# SWITCHING.net
KiCad netlist of a schematic drawn in Altium Designer
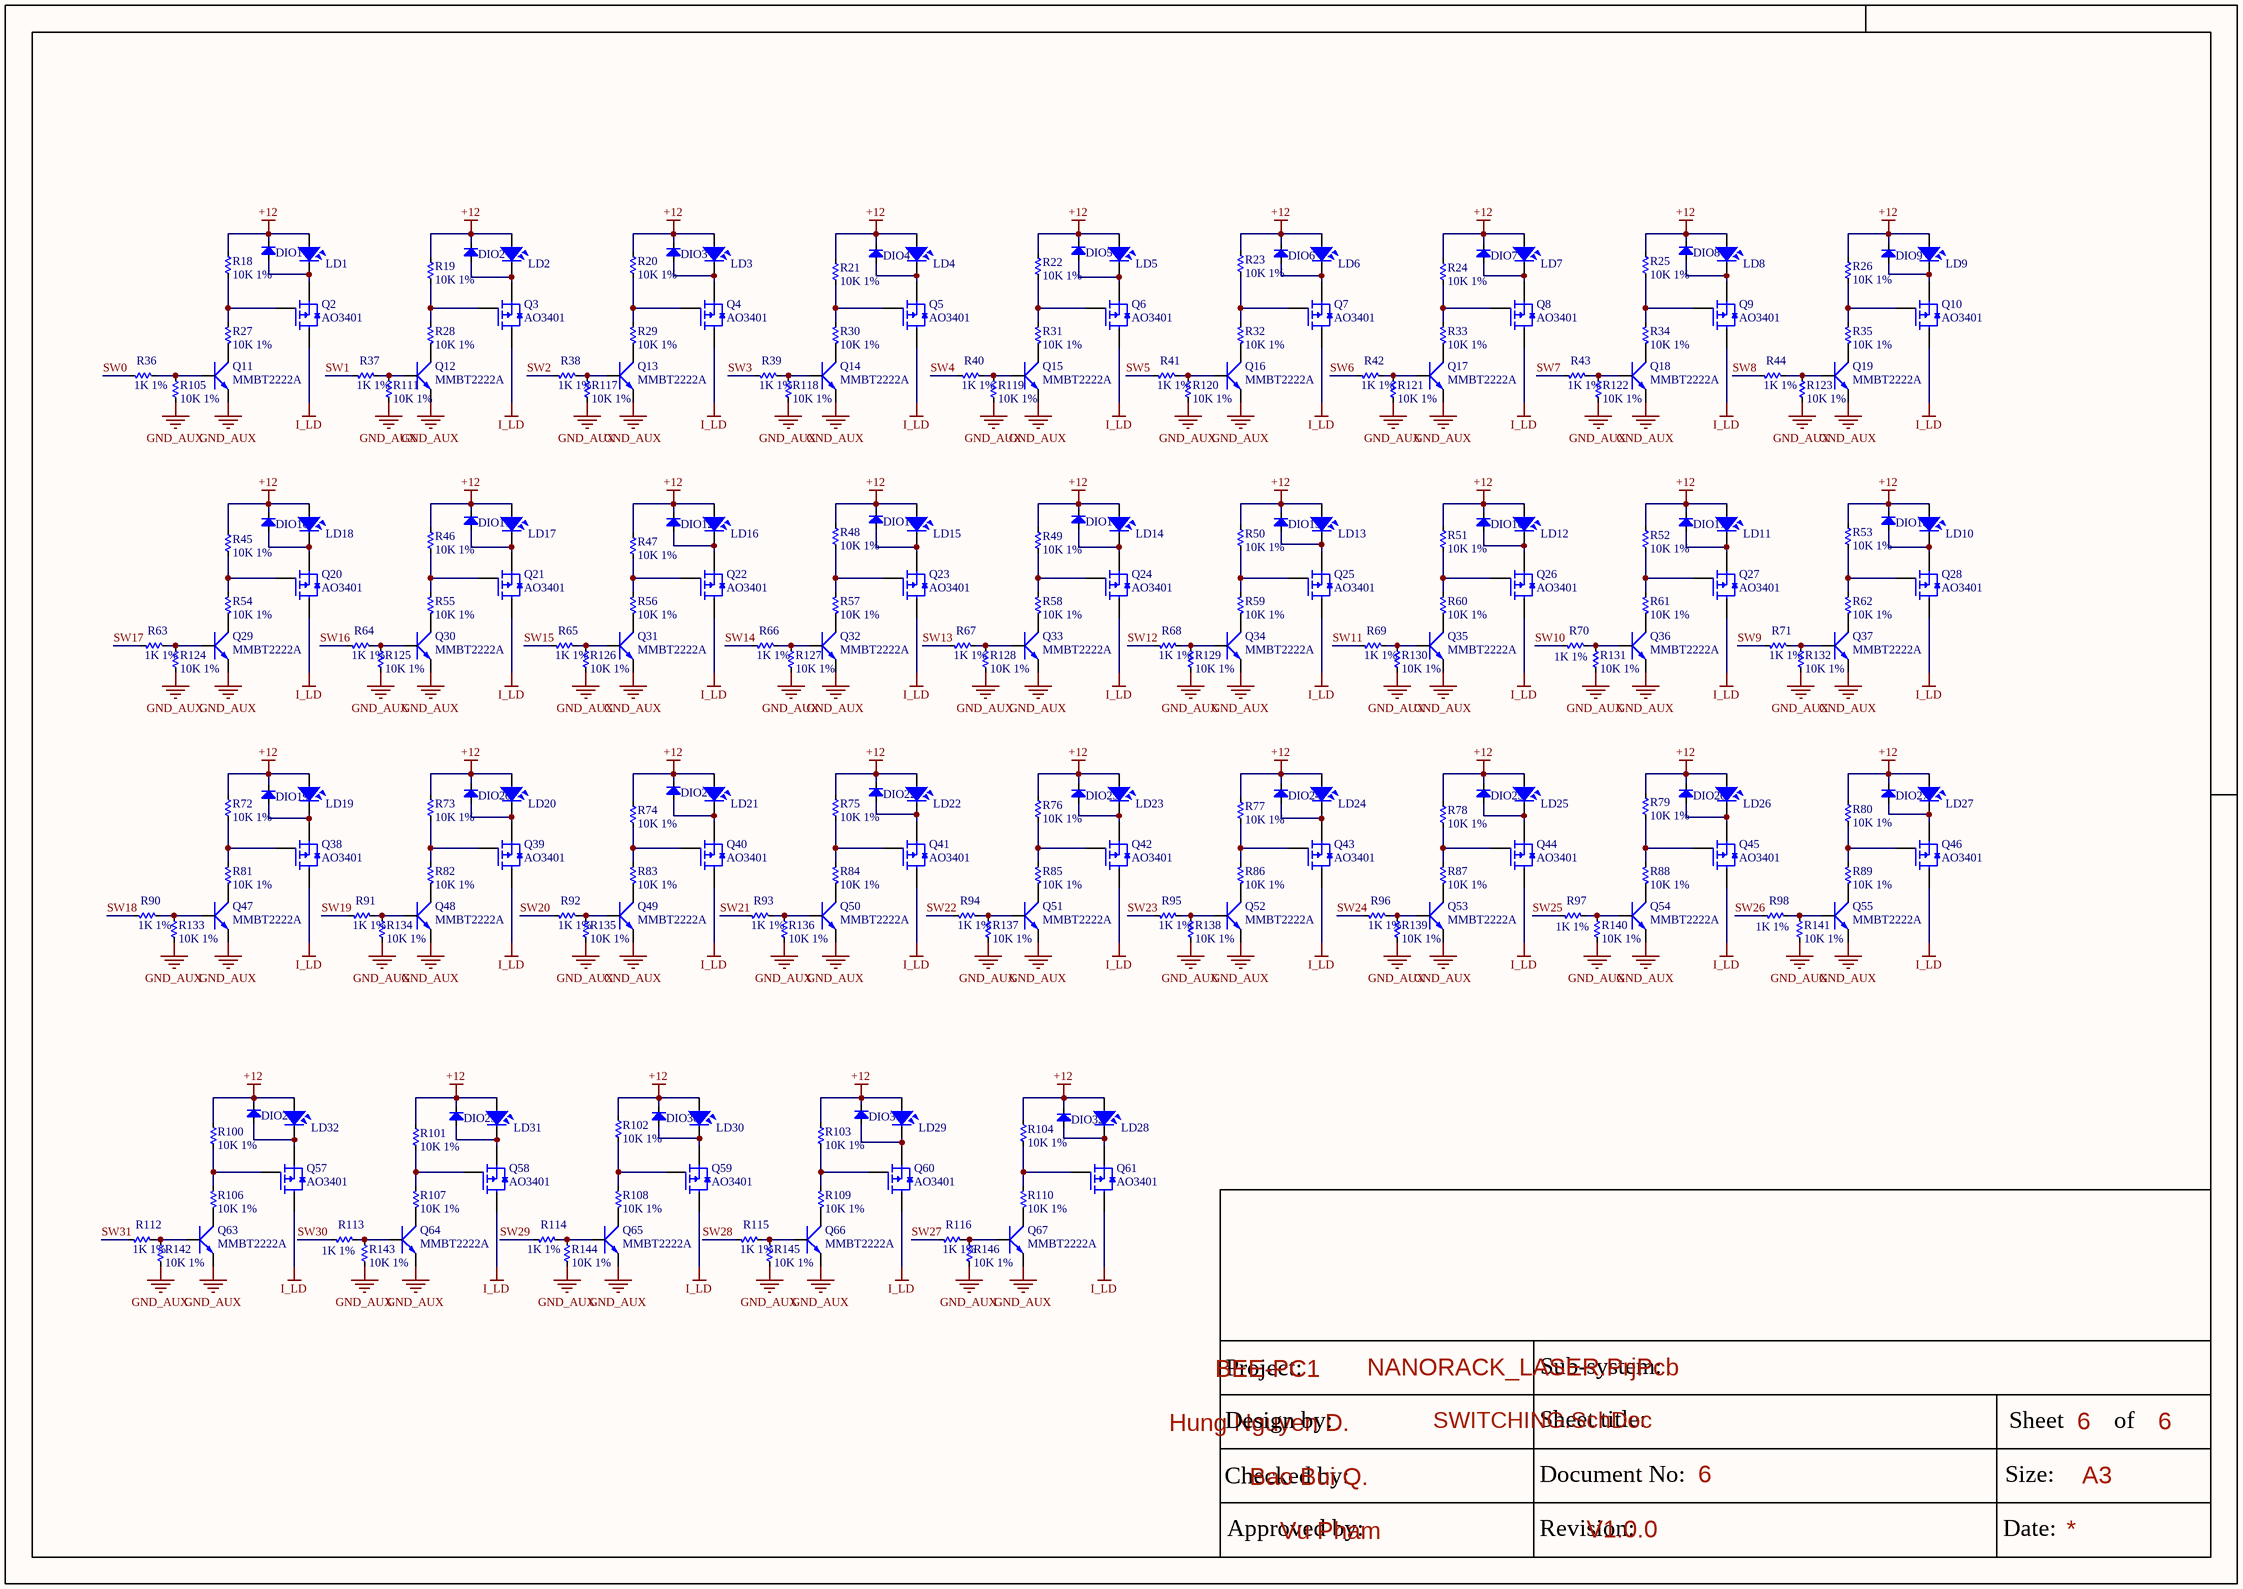
[diagram p0: SWITCHING.SchDoc]
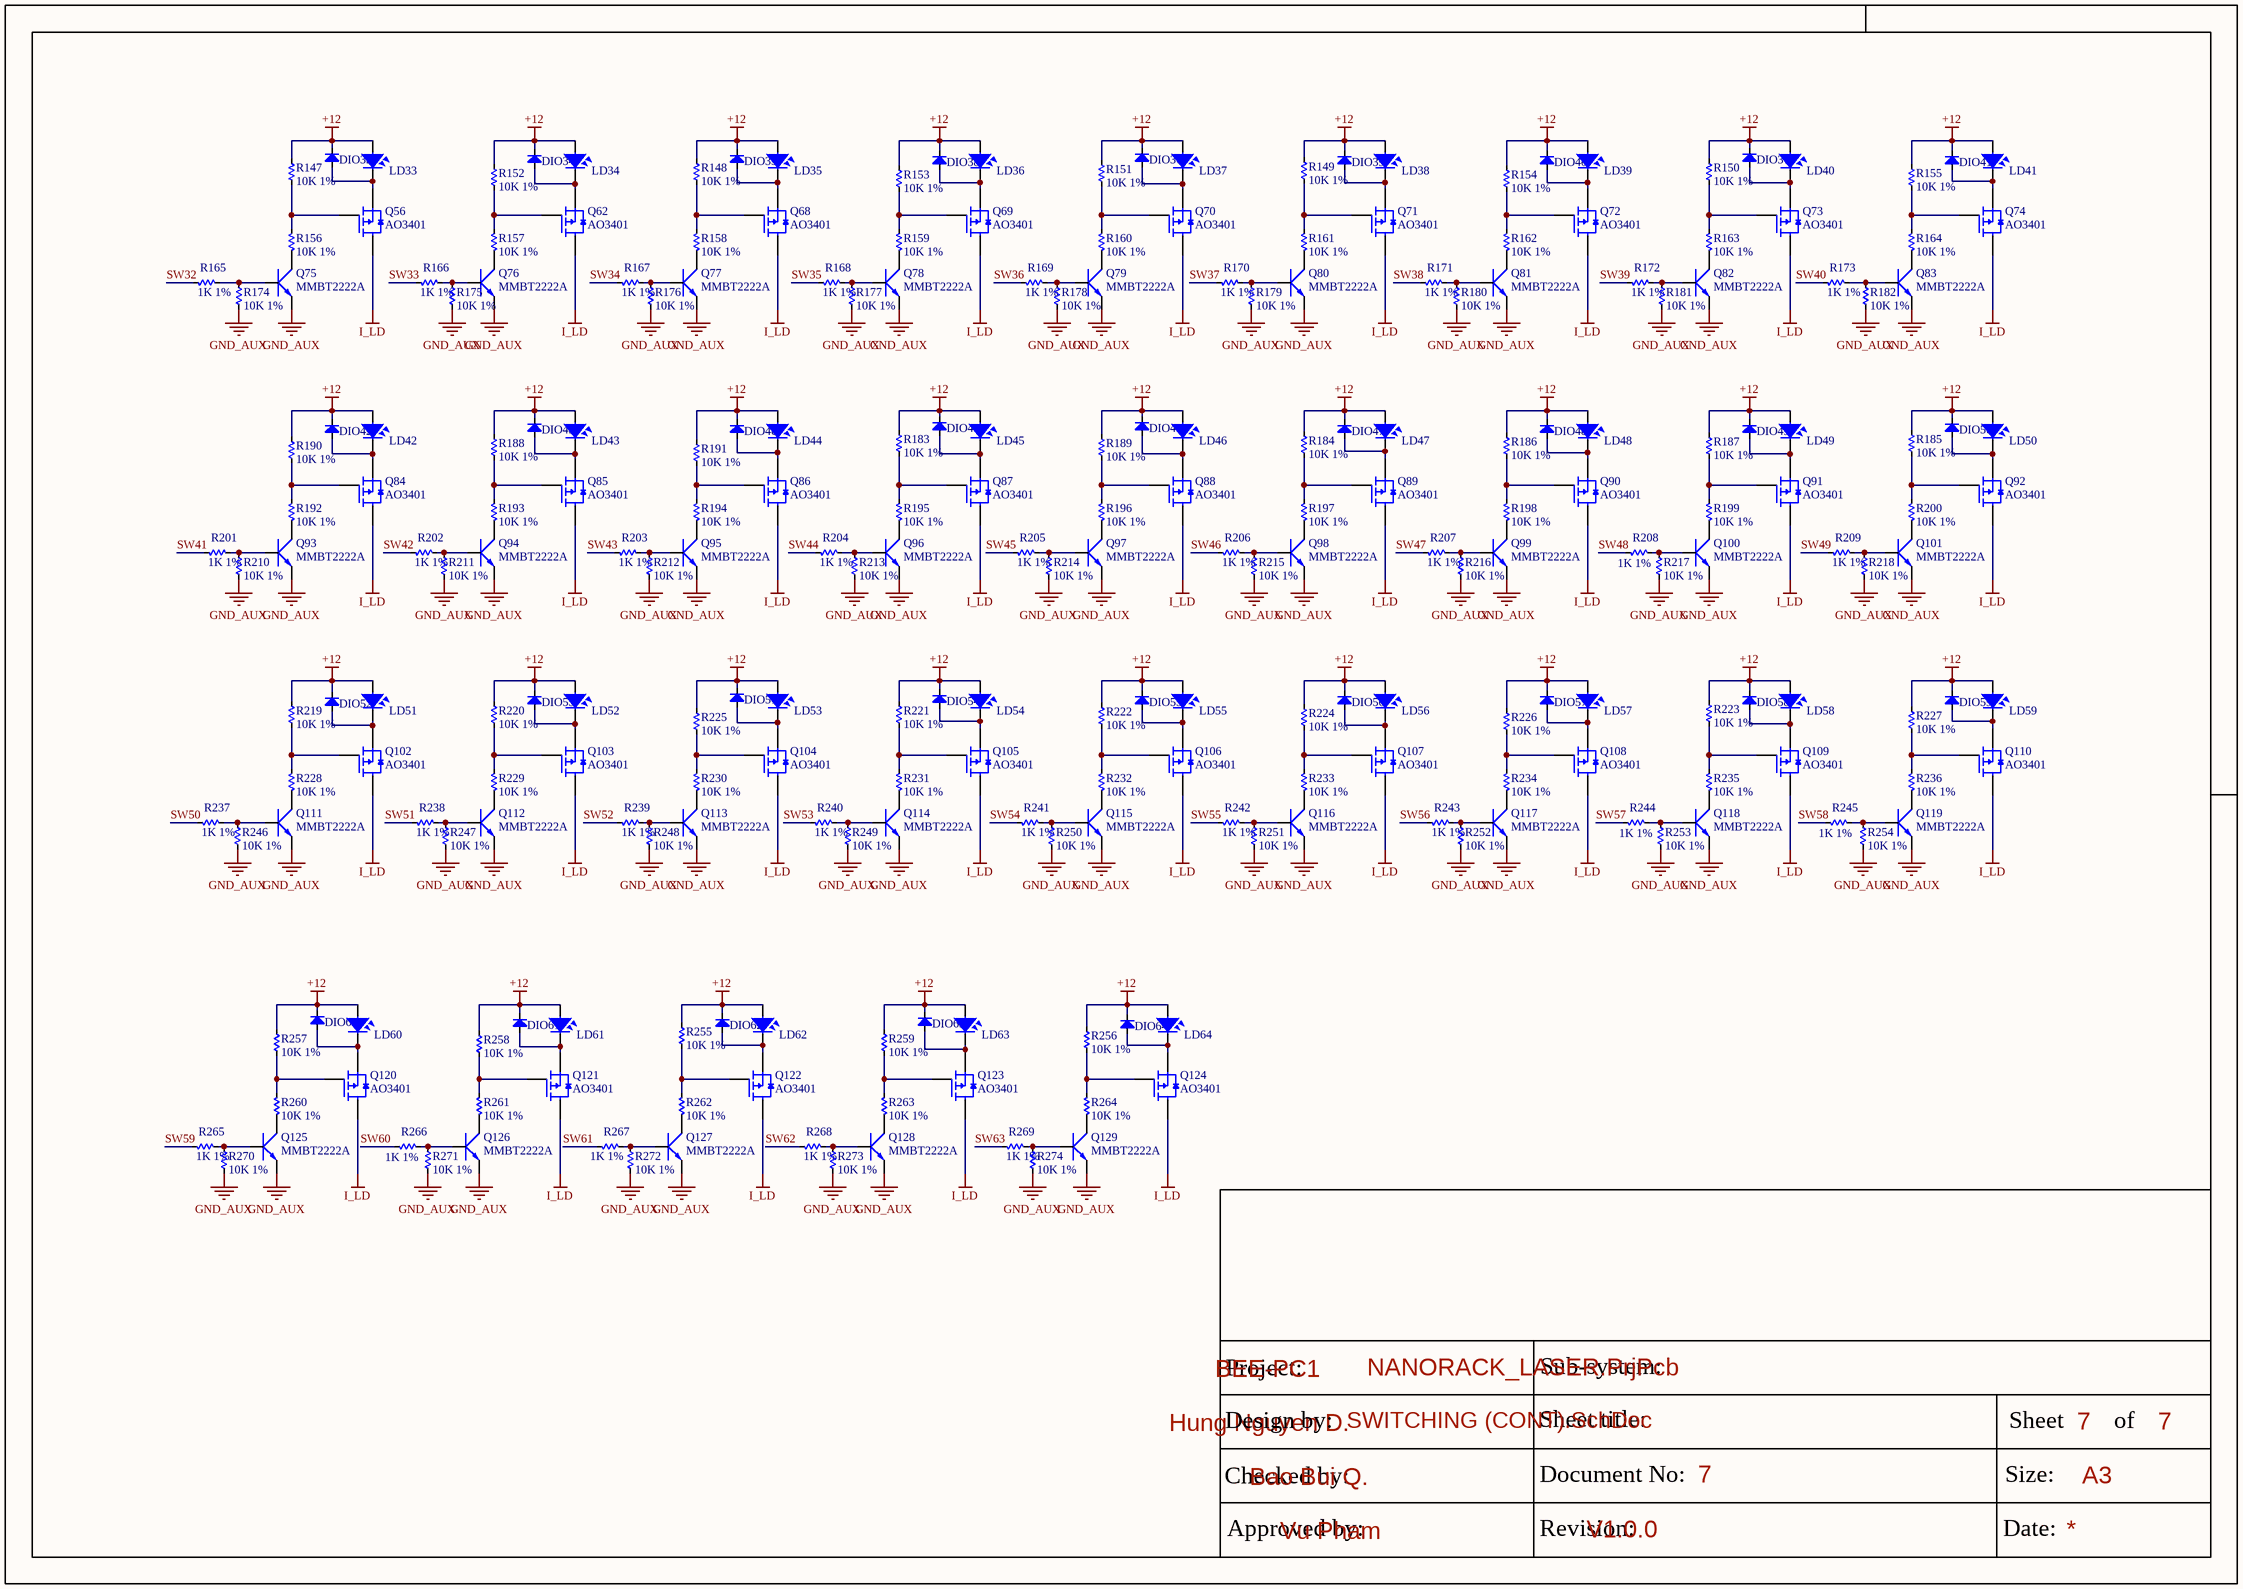
[diagram p1: SWITCHING (CONT).SchDoc]

(export (version "E")
  (design (tool "Eeschema 10.0.6"))
  (components
    (comp (ref "DIO33")
      (value "Diode SMD")
      (footprint "SOD23")
      (description "Default Diode")
      (fields (field (name "PUBLISHER") "Altium Limited"))
      (libsource (lib "Library") (part "Diode SMD"))
    )
    (comp (ref "DIO34")
      (value "Diode SMD")
      (footprint "SOD23")
      (description "Default Diode")
      (fields (field (name "PUBLISHER") "Altium Limited"))
      (libsource (lib "Library") (part "Diode SMD"))
    )
    (comp (ref "DIO35")
      (value "Diode SMD")
      (footprint "SOD23")
      (description "Default Diode")
      (fields (field (name "PUBLISHER") "Altium Limited"))
      (libsource (lib "Library") (part "Diode SMD"))
    )
    (comp (ref "DIO36")
      (value "Diode SMD")
      (footprint "SOD23")
      (description "Default Diode")
      (fields (field (name "PUBLISHER") "Altium Limited"))
      (libsource (lib "Library") (part "Diode SMD"))
    )
    (comp (ref "DIO37")
      (value "Diode SMD")
      (footprint "SOD23")
      (description "Default Diode")
      (fields (field (name "PUBLISHER") "Altium Limited"))
      (libsource (lib "Library") (part "Diode SMD"))
    )
    (comp (ref "DIO38")
      (value "Diode SMD")
      (footprint "SOD23")
      (description "Default Diode")
      (fields (field (name "PUBLISHER") "Altium Limited"))
      (libsource (lib "Library") (part "Diode SMD"))
    )
    (comp (ref "DIO39")
      (value "Diode SMD")
      (footprint "SOD23")
      (description "Default Diode")
      (fields (field (name "PUBLISHER") "Altium Limited"))
      (libsource (lib "Library") (part "Diode SMD"))
    )
    (comp (ref "DIO40")
      (value "Diode SMD")
      (footprint "SOD23")
      (description "Default Diode")
      (fields (field (name "PUBLISHER") "Altium Limited"))
      (libsource (lib "Library") (part "Diode SMD"))
    )
    (comp (ref "DIO41")
      (value "Diode SMD")
      (footprint "SOD23")
      (description "Default Diode")
      (fields (field (name "PUBLISHER") "Altium Limited"))
      (libsource (lib "Library") (part "Diode SMD"))
    )
    (comp (ref "DIO42")
      (value "Diode SMD")
      (footprint "SOD23")
      (description "Default Diode")
      (fields (field (name "PUBLISHER") "Altium Limited"))
      (libsource (lib "Library") (part "Diode SMD"))
    )
    (comp (ref "DIO43")
      (value "Diode SMD")
      (footprint "SOD23")
      (description "Default Diode")
      (fields (field (name "PUBLISHER") "Altium Limited"))
      (libsource (lib "Library") (part "Diode SMD"))
    )
    (comp (ref "DIO44")
      (value "Diode SMD")
      (footprint "SOD23")
      (description "Default Diode")
      (fields (field (name "PUBLISHER") "Altium Limited"))
      (libsource (lib "Library") (part "Diode SMD"))
    )
    (comp (ref "DIO45")
      (value "Diode SMD")
      (footprint "SOD23")
      (description "Default Diode")
      (fields (field (name "PUBLISHER") "Altium Limited"))
      (libsource (lib "Library") (part "Diode SMD"))
    )
    (comp (ref "DIO46")
      (value "Diode SMD")
      (footprint "SOD23")
      (description "Default Diode")
      (fields (field (name "PUBLISHER") "Altium Limited"))
      (libsource (lib "Library") (part "Diode SMD"))
    )
    (comp (ref "DIO47")
      (value "Diode SMD")
      (footprint "SOD23")
      (description "Default Diode")
      (fields (field (name "PUBLISHER") "Altium Limited"))
      (libsource (lib "Library") (part "Diode SMD"))
    )
    (comp (ref "DIO48")
      (value "Diode SMD")
      (footprint "SOD23")
      (description "Default Diode")
      (fields (field (name "PUBLISHER") "Altium Limited"))
      (libsource (lib "Library") (part "Diode SMD"))
    )
    (comp (ref "DIO49")
      (value "Diode SMD")
      (footprint "SOD23")
      (description "Default Diode")
      (fields (field (name "PUBLISHER") "Altium Limited"))
      (libsource (lib "Library") (part "Diode SMD"))
    )
    (comp (ref "DIO50")
      (value "Diode SMD")
      (footprint "SOD23")
      (description "Default Diode")
      (fields (field (name "PUBLISHER") "Altium Limited"))
      (libsource (lib "Library") (part "Diode SMD"))
    )
    (comp (ref "DIO51")
      (value "Diode SMD")
      (footprint "SOD23")
      (description "Default Diode")
      (fields (field (name "PUBLISHER") "Altium Limited"))
      (libsource (lib "Library") (part "Diode SMD"))
    )
    (comp (ref "DIO52")
      (value "Diode SMD")
      (footprint "SOD23")
      (description "Default Diode")
      (fields (field (name "PUBLISHER") "Altium Limited"))
      (libsource (lib "Library") (part "Diode SMD"))
    )
    (comp (ref "DIO53")
      (value "Diode SMD")
      (footprint "SOD23")
      (description "Default Diode")
      (fields (field (name "PUBLISHER") "Altium Limited"))
      (libsource (lib "Library") (part "Diode SMD"))
    )
    (comp (ref "DIO54")
      (value "Diode SMD")
      (footprint "SOD23")
      (description "Default Diode")
      (fields (field (name "PUBLISHER") "Altium Limited"))
      (libsource (lib "Library") (part "Diode SMD"))
    )
    (comp (ref "DIO55")
      (value "Diode SMD")
      (footprint "SOD23")
      (description "Default Diode")
      (fields (field (name "PUBLISHER") "Altium Limited"))
      (libsource (lib "Library") (part "Diode SMD"))
    )
    (comp (ref "DIO56")
      (value "Diode SMD")
      (footprint "SOD23")
      (description "Default Diode")
      (fields (field (name "PUBLISHER") "Altium Limited"))
      (libsource (lib "Library") (part "Diode SMD"))
    )
    (comp (ref "DIO57")
      (value "Diode SMD")
      (footprint "SOD23")
      (description "Default Diode")
      (fields (field (name "PUBLISHER") "Altium Limited"))
      (libsource (lib "Library") (part "Diode SMD"))
    )
    (comp (ref "DIO58")
      (value "Diode SMD")
      (footprint "SOD23")
      (description "Default Diode")
      (fields (field (name "PUBLISHER") "Altium Limited"))
      (libsource (lib "Library") (part "Diode SMD"))
    )
    (comp (ref "DIO59")
      (value "Diode SMD")
      (footprint "SOD23")
      (description "Default Diode")
      (fields (field (name "PUBLISHER") "Altium Limited"))
      (libsource (lib "Library") (part "Diode SMD"))
    )
    (comp (ref "DIO60")
      (value "Diode SMD")
      (footprint "SOD23")
      (description "Default Diode")
      (fields (field (name "PUBLISHER") "Altium Limited"))
      (libsource (lib "Library") (part "Diode SMD"))
    )
    (comp (ref "DIO61")
      (value "Diode SMD")
      (footprint "SOD23")
      (description "Default Diode")
      (fields (field (name "PUBLISHER") "Altium Limited"))
      (libsource (lib "Library") (part "Diode SMD"))
    )
    (comp (ref "DIO62")
      (value "Diode SMD")
      (footprint "SOD23")
      (description "Default Diode")
      (fields (field (name "PUBLISHER") "Altium Limited"))
      (libsource (lib "Library") (part "Diode SMD"))
    )
    (comp (ref "DIO63")
      (value "Diode SMD")
      (footprint "SOD23")
      (description "Default Diode")
      (fields (field (name "PUBLISHER") "Altium Limited"))
      (libsource (lib "Library") (part "Diode SMD"))
    )
    (comp (ref "DIO64")
      (value "Diode SMD")
      (footprint "SOD23")
      (description "Default Diode")
      (fields (field (name "PUBLISHER") "Altium Limited"))
      (libsource (lib "Library") (part "Diode SMD"))
    )
    (comp (ref "LD33") (value "LaserDiode") (footprint "LASER") (libsource (lib "Library") (part "LD")))
    (comp (ref "LD34") (value "LaserDiode") (footprint "LASER") (libsource (lib "Library") (part "LD")))
    (comp (ref "LD35") (value "LaserDiode") (footprint "LASER") (libsource (lib "Library") (part "LD")))
    (comp (ref "LD36") (value "LaserDiode") (footprint "LASER") (libsource (lib "Library") (part "LD")))
    (comp (ref "LD37") (value "LaserDiode") (footprint "LASER") (libsource (lib "Library") (part "LD")))
    (comp (ref "LD38") (value "LaserDiode") (footprint "LASER") (libsource (lib "Library") (part "LD")))
    (comp (ref "LD39") (value "LaserDiode") (footprint "LASER") (libsource (lib "Library") (part "LD")))
    (comp (ref "LD40") (value "LaserDiode") (footprint "LASER") (libsource (lib "Library") (part "LD")))
    (comp (ref "LD41") (value "LaserDiode") (footprint "LASER") (libsource (lib "Library") (part "LD")))
    (comp (ref "LD42") (value "LaserDiode") (footprint "LASER") (libsource (lib "Library") (part "LD")))
    (comp (ref "LD43") (value "LaserDiode") (footprint "LASER") (libsource (lib "Library") (part "LD")))
    (comp (ref "LD44") (value "LaserDiode") (footprint "LASER") (libsource (lib "Library") (part "LD")))
    (comp (ref "LD45") (value "LaserDiode") (footprint "LASER") (libsource (lib "Library") (part "LD")))
    (comp (ref "LD46") (value "LaserDiode") (footprint "LASER") (libsource (lib "Library") (part "LD")))
    (comp (ref "LD47") (value "LaserDiode") (footprint "LASER") (libsource (lib "Library") (part "LD")))
    (comp (ref "LD48") (value "LaserDiode") (footprint "LASER") (libsource (lib "Library") (part "LD")))
    (comp (ref "LD49") (value "LaserDiode") (footprint "LASER") (libsource (lib "Library") (part "LD")))
    (comp (ref "LD50") (value "LaserDiode") (footprint "LASER") (libsource (lib "Library") (part "LD")))
    (comp (ref "LD51") (value "LaserDiode") (footprint "LASER") (libsource (lib "Library") (part "LD")))
    (comp (ref "LD52") (value "LaserDiode") (footprint "LASER") (libsource (lib "Library") (part "LD")))
    (comp (ref "LD53") (value "LaserDiode") (footprint "LASER") (libsource (lib "Library") (part "LD")))
    (comp (ref "LD54") (value "LaserDiode") (footprint "LASER") (libsource (lib "Library") (part "LD")))
    (comp (ref "LD55") (value "LaserDiode") (footprint "LASER") (libsource (lib "Library") (part "LD")))
    (comp (ref "LD56") (value "LaserDiode") (footprint "LASER") (libsource (lib "Library") (part "LD")))
    (comp (ref "LD57") (value "LaserDiode") (footprint "LASER") (libsource (lib "Library") (part "LD")))
    (comp (ref "LD58") (value "LaserDiode") (footprint "LASER") (libsource (lib "Library") (part "LD")))
    (comp (ref "LD59") (value "LaserDiode") (footprint "LASER") (libsource (lib "Library") (part "LD")))
    (comp (ref "LD60") (value "LaserDiode") (footprint "LASER") (libsource (lib "Library") (part "LD")))
    (comp (ref "LD61") (value "LaserDiode") (footprint "LASER") (libsource (lib "Library") (part "LD")))
    (comp (ref "LD62") (value "LaserDiode") (footprint "LASER") (libsource (lib "Library") (part "LD")))
    (comp (ref "LD63") (value "LaserDiode") (footprint "LASER") (libsource (lib "Library") (part "LD")))
    (comp (ref "LD64") (value "LaserDiode") (footprint "LASER") (libsource (lib "Library") (part "LD")))
    (comp (ref "Q56") (value "AO3401") (footprint "SOT23-123") (libsource (lib "Library") (part "FET-P")))
    (comp (ref "Q62") (value "AO3401") (footprint "SOT23-123") (libsource (lib "Library") (part "FET-P")))
    (comp (ref "Q68") (value "AO3401") (footprint "SOT23-123") (libsource (lib "Library") (part "FET-P")))
    (comp (ref "Q69") (value "AO3401") (footprint "SOT23-123") (libsource (lib "Library") (part "FET-P")))
    (comp (ref "Q70") (value "AO3401") (footprint "SOT23-123") (libsource (lib "Library") (part "FET-P")))
    (comp (ref "Q71") (value "AO3401") (footprint "SOT23-123") (libsource (lib "Library") (part "FET-P")))
    (comp (ref "Q72") (value "AO3401") (footprint "SOT23-123") (libsource (lib "Library") (part "FET-P")))
    (comp (ref "Q73") (value "AO3401") (footprint "SOT23-123") (libsource (lib "Library") (part "FET-P")))
    (comp (ref "Q74") (value "AO3401") (footprint "SOT23-123") (libsource (lib "Library") (part "FET-P")))
    (comp (ref "Q75")
      (value "MMBT2222A")
      (footprint "SOT23-132")
      (description "SOT23-3")
      (libsource (lib "Library") (part "2SC1815"))
    )
    (comp (ref "Q76")
      (value "MMBT2222A")
      (footprint "SOT23-132")
      (description "SOT23-3")
      (libsource (lib "Library") (part "2SC1815"))
    )
    (comp (ref "Q77")
      (value "MMBT2222A")
      (footprint "SOT23-132")
      (description "SOT23-3")
      (libsource (lib "Library") (part "2SC1815"))
    )
    (comp (ref "Q78")
      (value "MMBT2222A")
      (footprint "SOT23-132")
      (description "SOT23-3")
      (libsource (lib "Library") (part "2SC1815"))
    )
    (comp (ref "Q79")
      (value "MMBT2222A")
      (footprint "SOT23-132")
      (description "SOT23-3")
      (libsource (lib "Library") (part "2SC1815"))
    )
    (comp (ref "Q80")
      (value "MMBT2222A")
      (footprint "SOT23-132")
      (description "SOT23-3")
      (libsource (lib "Library") (part "2SC1815"))
    )
    (comp (ref "Q81")
      (value "MMBT2222A")
      (footprint "SOT23-132")
      (description "SOT23-3")
      (libsource (lib "Library") (part "2SC1815"))
    )
    (comp (ref "Q82")
      (value "MMBT2222A")
      (footprint "SOT23-132")
      (description "SOT23-3")
      (libsource (lib "Library") (part "2SC1815"))
    )
    (comp (ref "Q83")
      (value "MMBT2222A")
      (footprint "SOT23-132")
      (description "SOT23-3")
      (libsource (lib "Library") (part "2SC1815"))
    )
    (comp (ref "Q84") (value "AO3401") (footprint "SOT23-123") (libsource (lib "Library") (part "FET-P")))
    (comp (ref "Q85") (value "AO3401") (footprint "SOT23-123") (libsource (lib "Library") (part "FET-P")))
    (comp (ref "Q86") (value "AO3401") (footprint "SOT23-123") (libsource (lib "Library") (part "FET-P")))
    (comp (ref "Q87") (value "AO3401") (footprint "SOT23-123") (libsource (lib "Library") (part "FET-P")))
    (comp (ref "Q88") (value "AO3401") (footprint "SOT23-123") (libsource (lib "Library") (part "FET-P")))
    (comp (ref "Q89") (value "AO3401") (footprint "SOT23-123") (libsource (lib "Library") (part "FET-P")))
    (comp (ref "Q90") (value "AO3401") (footprint "SOT23-123") (libsource (lib "Library") (part "FET-P")))
    (comp (ref "Q91") (value "AO3401") (footprint "SOT23-123") (libsource (lib "Library") (part "FET-P")))
    (comp (ref "Q92") (value "AO3401") (footprint "SOT23-123") (libsource (lib "Library") (part "FET-P")))
    (comp (ref "Q93")
      (value "MMBT2222A")
      (footprint "SOT23-132")
      (description "SOT23-3")
      (libsource (lib "Library") (part "2SC1815"))
    )
    (comp (ref "Q94")
      (value "MMBT2222A")
      (footprint "SOT23-132")
      (description "SOT23-3")
      (libsource (lib "Library") (part "2SC1815"))
    )
    (comp (ref "Q95")
      (value "MMBT2222A")
      (footprint "SOT23-132")
      (description "SOT23-3")
      (libsource (lib "Library") (part "2SC1815"))
    )
    (comp (ref "Q96")
      (value "MMBT2222A")
      (footprint "SOT23-132")
      (description "SOT23-3")
      (libsource (lib "Library") (part "2SC1815"))
    )
    (comp (ref "Q97")
      (value "MMBT2222A")
      (footprint "SOT23-132")
      (description "SOT23-3")
      (libsource (lib "Library") (part "2SC1815"))
    )
    (comp (ref "Q98")
      (value "MMBT2222A")
      (footprint "SOT23-132")
      (description "SOT23-3")
      (libsource (lib "Library") (part "2SC1815"))
    )
    (comp (ref "Q99")
      (value "MMBT2222A")
      (footprint "SOT23-132")
      (description "SOT23-3")
      (libsource (lib "Library") (part "2SC1815"))
    )
    (comp (ref "Q100")
      (value "MMBT2222A")
      (footprint "SOT23-132")
      (description "SOT23-3")
      (libsource (lib "Library") (part "2SC1815"))
    )
    (comp (ref "Q101")
      (value "MMBT2222A")
      (footprint "SOT23-132")
      (description "SOT23-3")
      (libsource (lib "Library") (part "2SC1815"))
    )
    (comp (ref "Q102") (value "AO3401") (footprint "SOT23-123") (libsource (lib "Library") (part "FET-P")))
    (comp (ref "Q103") (value "AO3401") (footprint "SOT23-123") (libsource (lib "Library") (part "FET-P")))
    (comp (ref "Q104") (value "AO3401") (footprint "SOT23-123") (libsource (lib "Library") (part "FET-P")))
    (comp (ref "Q105") (value "AO3401") (footprint "SOT23-123") (libsource (lib "Library") (part "FET-P")))
    (comp (ref "Q106") (value "AO3401") (footprint "SOT23-123") (libsource (lib "Library") (part "FET-P")))
    (comp (ref "Q107") (value "AO3401") (footprint "SOT23-123") (libsource (lib "Library") (part "FET-P")))
    (comp (ref "Q108") (value "AO3401") (footprint "SOT23-123") (libsource (lib "Library") (part "FET-P")))
    (comp (ref "Q109") (value "AO3401") (footprint "SOT23-123") (libsource (lib "Library") (part "FET-P")))
    (comp (ref "Q110") (value "AO3401") (footprint "SOT23-123") (libsource (lib "Library") (part "FET-P")))
    (comp (ref "Q111")
      (value "MMBT2222A")
      (footprint "SOT23-132")
      (description "SOT23-3")
      (libsource (lib "Library") (part "2SC1815"))
    )
    (comp (ref "Q112")
      (value "MMBT2222A")
      (footprint "SOT23-132")
      (description "SOT23-3")
      (libsource (lib "Library") (part "2SC1815"))
    )
    (comp (ref "Q113")
      (value "MMBT2222A")
      (footprint "SOT23-132")
      (description "SOT23-3")
      (libsource (lib "Library") (part "2SC1815"))
    )
    (comp (ref "Q114")
      (value "MMBT2222A")
      (footprint "SOT23-132")
      (description "SOT23-3")
      (libsource (lib "Library") (part "2SC1815"))
    )
    (comp (ref "Q115")
      (value "MMBT2222A")
      (footprint "SOT23-132")
      (description "SOT23-3")
      (libsource (lib "Library") (part "2SC1815"))
    )
    (comp (ref "Q116")
      (value "MMBT2222A")
      (footprint "SOT23-132")
      (description "SOT23-3")
      (libsource (lib "Library") (part "2SC1815"))
    )
    (comp (ref "Q117")
      (value "MMBT2222A")
      (footprint "SOT23-132")
      (description "SOT23-3")
      (libsource (lib "Library") (part "2SC1815"))
    )
    (comp (ref "Q118")
      (value "MMBT2222A")
      (footprint "SOT23-132")
      (description "SOT23-3")
      (libsource (lib "Library") (part "2SC1815"))
    )
    (comp (ref "Q119")
      (value "MMBT2222A")
      (footprint "SOT23-132")
      (description "SOT23-3")
      (libsource (lib "Library") (part "2SC1815"))
    )
    (comp (ref "Q120") (value "AO3401") (footprint "SOT23-123") (libsource (lib "Library") (part "FET-P")))
    (comp (ref "Q121") (value "AO3401") (footprint "SOT23-123") (libsource (lib "Library") (part "FET-P")))
    (comp (ref "Q122") (value "AO3401") (footprint "SOT23-123") (libsource (lib "Library") (part "FET-P")))
    (comp (ref "Q123") (value "AO3401") (footprint "SOT23-123") (libsource (lib "Library") (part "FET-P")))
    (comp (ref "Q124") (value "AO3401") (footprint "SOT23-123") (libsource (lib "Library") (part "FET-P")))
    (comp (ref "Q125")
      (value "MMBT2222A")
      (footprint "SOT23-132")
      (description "SOT23-3")
      (libsource (lib "Library") (part "2SC1815"))
    )
    (comp (ref "Q126")
      (value "MMBT2222A")
      (footprint "SOT23-132")
      (description "SOT23-3")
      (libsource (lib "Library") (part "2SC1815"))
    )
    (comp (ref "Q127")
      (value "MMBT2222A")
      (footprint "SOT23-132")
      (description "SOT23-3")
      (libsource (lib "Library") (part "2SC1815"))
    )
    (comp (ref "Q128")
      (value "MMBT2222A")
      (footprint "SOT23-132")
      (description "SOT23-3")
      (libsource (lib "Library") (part "2SC1815"))
    )
    (comp (ref "Q129")
      (value "MMBT2222A")
      (footprint "SOT23-132")
      (description "SOT23-3")
      (libsource (lib "Library") (part "2SC1815"))
    )
    (comp (ref "R147")
      (value "10K 1%")
      (footprint "RES-SMD-0603")
      (description "0603")
      (fields
        (field (name "MANUFACTURER") "Generic Components")
        (field (name "PUBLISHER") "Altium Hobart Technology Centre")
      )
      (libsource (lib "Library") (part "Res-SMD"))
    )
    (comp (ref "R148")
      (value "10K 1%")
      (footprint "RES-SMD-0603")
      (description "0603")
      (fields
        (field (name "MANUFACTURER") "Generic Components")
        (field (name "PUBLISHER") "Altium Hobart Technology Centre")
      )
      (libsource (lib "Library") (part "Res-SMD"))
    )
    (comp (ref "R149")
      (value "10K 1%")
      (footprint "RES-SMD-0603")
      (description "0603")
      (fields
        (field (name "MANUFACTURER") "Generic Components")
        (field (name "PUBLISHER") "Altium Hobart Technology Centre")
      )
      (libsource (lib "Library") (part "Res-SMD"))
    )
    (comp (ref "R150")
      (value "10K 1%")
      (footprint "RES-SMD-0603")
      (description "0603")
      (fields
        (field (name "MANUFACTURER") "Generic Components")
        (field (name "PUBLISHER") "Altium Hobart Technology Centre")
      )
      (libsource (lib "Library") (part "Res-SMD"))
    )
    (comp (ref "R151")
      (value "10K 1%")
      (footprint "RES-SMD-0603")
      (description "0603")
      (fields
        (field (name "MANUFACTURER") "Generic Components")
        (field (name "PUBLISHER") "Altium Hobart Technology Centre")
      )
      (libsource (lib "Library") (part "Res-SMD"))
    )
    (comp (ref "R152")
      (value "10K 1%")
      (footprint "RES-SMD-0603")
      (description "0603")
      (fields
        (field (name "MANUFACTURER") "Generic Components")
        (field (name "PUBLISHER") "Altium Hobart Technology Centre")
      )
      (libsource (lib "Library") (part "Res-SMD"))
    )
    (comp (ref "R153")
      (value "10K 1%")
      (footprint "RES-SMD-0603")
      (description "0603")
      (fields
        (field (name "MANUFACTURER") "Generic Components")
        (field (name "PUBLISHER") "Altium Hobart Technology Centre")
      )
      (libsource (lib "Library") (part "Res-SMD"))
    )
    (comp (ref "R154")
      (value "10K 1%")
      (footprint "RES-SMD-0603")
      (description "0603")
      (fields
        (field (name "MANUFACTURER") "Generic Components")
        (field (name "PUBLISHER") "Altium Hobart Technology Centre")
      )
      (libsource (lib "Library") (part "Res-SMD"))
    )
    (comp (ref "R155")
      (value "10K 1%")
      (footprint "RES-SMD-0603")
      (description "0603")
      (fields
        (field (name "MANUFACTURER") "Generic Components")
        (field (name "PUBLISHER") "Altium Hobart Technology Centre")
      )
      (libsource (lib "Library") (part "Res-SMD"))
    )
    (comp (ref "R156")
      (value "10K 1%")
      (footprint "RES-SMD-0603")
      (description "0603")
      (fields
        (field (name "MANUFACTURER") "Generic Components")
        (field (name "PUBLISHER") "Altium Hobart Technology Centre")
      )
      (libsource (lib "Library") (part "Res-SMD"))
    )
    (comp (ref "R157")
      (value "10K 1%")
      (footprint "RES-SMD-0603")
      (description "0603")
      (fields
        (field (name "MANUFACTURER") "Generic Components")
        (field (name "PUBLISHER") "Altium Hobart Technology Centre")
      )
      (libsource (lib "Library") (part "Res-SMD"))
    )
    (comp (ref "R158")
      (value "10K 1%")
      (footprint "RES-SMD-0603")
      (description "0603")
      (fields
        (field (name "MANUFACTURER") "Generic Components")
        (field (name "PUBLISHER") "Altium Hobart Technology Centre")
      )
      (libsource (lib "Library") (part "Res-SMD"))
    )
    (comp (ref "R159")
      (value "10K 1%")
      (footprint "RES-SMD-0603")
      (description "0603")
      (fields
        (field (name "MANUFACTURER") "Generic Components")
        (field (name "PUBLISHER") "Altium Hobart Technology Centre")
      )
      (libsource (lib "Library") (part "Res-SMD"))
    )
    (comp (ref "R160")
      (value "10K 1%")
      (footprint "RES-SMD-0603")
      (description "0603")
      (fields
        (field (name "MANUFACTURER") "Generic Components")
        (field (name "PUBLISHER") "Altium Hobart Technology Centre")
      )
      (libsource (lib "Library") (part "Res-SMD"))
    )
    (comp (ref "R161")
      (value "10K 1%")
      (footprint "RES-SMD-0603")
      (description "0603")
      (fields
        (field (name "MANUFACTURER") "Generic Components")
        (field (name "PUBLISHER") "Altium Hobart Technology Centre")
      )
      (libsource (lib "Library") (part "Res-SMD"))
    )
    (comp (ref "R162")
      (value "10K 1%")
      (footprint "RES-SMD-0603")
      (description "0603")
      (fields
        (field (name "MANUFACTURER") "Generic Components")
        (field (name "PUBLISHER") "Altium Hobart Technology Centre")
      )
      (libsource (lib "Library") (part "Res-SMD"))
    )
    (comp (ref "R163")
      (value "10K 1%")
      (footprint "RES-SMD-0603")
      (description "0603")
      (fields
        (field (name "MANUFACTURER") "Generic Components")
        (field (name "PUBLISHER") "Altium Hobart Technology Centre")
      )
      (libsource (lib "Library") (part "Res-SMD"))
    )
    (comp (ref "R164")
      (value "10K 1%")
      (footprint "RES-SMD-0603")
      (description "0603")
      (fields
        (field (name "MANUFACTURER") "Generic Components")
        (field (name "PUBLISHER") "Altium Hobart Technology Centre")
      )
      (libsource (lib "Library") (part "Res-SMD"))
    )
    (comp (ref "R165")
      (value "1K 1%")
      (footprint "RES-SMD-0603")
      (description "0603")
      (fields
        (field (name "MANUFACTURER") "Generic Components")
        (field (name "PUBLISHER") "Altium Hobart Technology Centre")
      )
      (libsource (lib "Library") (part "Res-SMD"))
    )
    (comp (ref "R166")
      (value "1K 1%")
      (footprint "RES-SMD-0603")
      (description "0603")
      (fields
        (field (name "MANUFACTURER") "Generic Components")
        (field (name "PUBLISHER") "Altium Hobart Technology Centre")
      )
      (libsource (lib "Library") (part "Res-SMD"))
    )
    (comp (ref "R167")
      (value "1K 1%")
      (footprint "RES-SMD-0603")
      (description "0603")
      (fields
        (field (name "MANUFACTURER") "Generic Components")
        (field (name "PUBLISHER") "Altium Hobart Technology Centre")
      )
      (libsource (lib "Library") (part "Res-SMD"))
    )
    (comp (ref "R168")
      (value "1K 1%")
      (footprint "RES-SMD-0603")
      (description "0603")
      (fields
        (field (name "MANUFACTURER") "Generic Components")
        (field (name "PUBLISHER") "Altium Hobart Technology Centre")
      )
      (libsource (lib "Library") (part "Res-SMD"))
    )
    (comp (ref "R169")
      (value "1K 1%")
      (footprint "RES-SMD-0603")
      (description "0603")
      (fields
        (field (name "MANUFACTURER") "Generic Components")
        (field (name "PUBLISHER") "Altium Hobart Technology Centre")
      )
      (libsource (lib "Library") (part "Res-SMD"))
    )
    (comp (ref "R170")
      (value "1K 1%")
      (footprint "RES-SMD-0603")
      (description "0603")
      (fields
        (field (name "MANUFACTURER") "Generic Components")
        (field (name "PUBLISHER") "Altium Hobart Technology Centre")
      )
      (libsource (lib "Library") (part "Res-SMD"))
    )
    (comp (ref "R171")
      (value "1K 1%")
      (footprint "RES-SMD-0603")
      (description "0603")
      (fields
        (field (name "MANUFACTURER") "Generic Components")
        (field (name "PUBLISHER") "Altium Hobart Technology Centre")
      )
      (libsource (lib "Library") (part "Res-SMD"))
    )
    (comp (ref "R172")
      (value "1K 1%")
      (footprint "RES-SMD-0603")
      (description "0603")
      (fields
        (field (name "MANUFACTURER") "Generic Components")
        (field (name "PUBLISHER") "Altium Hobart Technology Centre")
      )
      (libsource (lib "Library") (part "Res-SMD"))
    )
    (comp (ref "R173")
      (value "1K 1%")
      (footprint "RES-SMD-0603")
      (description "0603")
      (fields
        (field (name "MANUFACTURER") "Generic Components")
        (field (name "PUBLISHER") "Altium Hobart Technology Centre")
      )
      (libsource (lib "Library") (part "Res-SMD"))
    )
    (comp (ref "R174")
      (value "10K 1%")
      (footprint "RES-SMD-0603")
      (description "0603")
      (fields
        (field (name "MANUFACTURER") "Generic Components")
        (field (name "PUBLISHER") "Altium Hobart Technology Centre")
      )
      (libsource (lib "Library") (part "Res-SMD"))
    )
    (comp (ref "R175")
      (value "10K 1%")
      (footprint "RES-SMD-0603")
      (description "0603")
      (fields
        (field (name "MANUFACTURER") "Generic Components")
        (field (name "PUBLISHER") "Altium Hobart Technology Centre")
      )
      (libsource (lib "Library") (part "Res-SMD"))
    )
    (comp (ref "R176")
      (value "10K 1%")
      (footprint "RES-SMD-0603")
      (description "0603")
      (fields
        (field (name "MANUFACTURER") "Generic Components")
        (field (name "PUBLISHER") "Altium Hobart Technology Centre")
      )
      (libsource (lib "Library") (part "Res-SMD"))
    )
    (comp (ref "R177")
      (value "10K 1%")
      (footprint "RES-SMD-0603")
      (description "0603")
      (fields
        (field (name "MANUFACTURER") "Generic Components")
        (field (name "PUBLISHER") "Altium Hobart Technology Centre")
      )
      (libsource (lib "Library") (part "Res-SMD"))
    )
    (comp (ref "R178")
      (value "10K 1%")
      (footprint "RES-SMD-0603")
      (description "0603")
      (fields
        (field (name "MANUFACTURER") "Generic Components")
        (field (name "PUBLISHER") "Altium Hobart Technology Centre")
      )
      (libsource (lib "Library") (part "Res-SMD"))
    )
    (comp (ref "R179")
      (value "10K 1%")
      (footprint "RES-SMD-0603")
      (description "0603")
      (fields
        (field (name "MANUFACTURER") "Generic Components")
        (field (name "PUBLISHER") "Altium Hobart Technology Centre")
      )
      (libsource (lib "Library") (part "Res-SMD"))
    )
    (comp (ref "R180")
      (value "10K 1%")
      (footprint "RES-SMD-0603")
      (description "0603")
      (fields
        (field (name "MANUFACTURER") "Generic Components")
        (field (name "PUBLISHER") "Altium Hobart Technology Centre")
      )
      (libsource (lib "Library") (part "Res-SMD"))
    )
    (comp (ref "R181")
      (value "10K 1%")
      (footprint "RES-SMD-0603")
      (description "0603")
      (fields
        (field (name "MANUFACTURER") "Generic Components")
        (field (name "PUBLISHER") "Altium Hobart Technology Centre")
      )
      (libsource (lib "Library") (part "Res-SMD"))
    )
    (comp (ref "R182")
      (value "10K 1%")
      (footprint "RES-SMD-0603")
      (description "0603")
      (fields
        (field (name "MANUFACTURER") "Generic Components")
        (field (name "PUBLISHER") "Altium Hobart Technology Centre")
      )
      (libsource (lib "Library") (part "Res-SMD"))
    )
    (comp (ref "R183")
      (value "10K 1%")
      (footprint "RES-SMD-0603")
      (description "0603")
      (fields
        (field (name "MANUFACTURER") "Generic Components")
        (field (name "PUBLISHER") "Altium Hobart Technology Centre")
      )
      (libsource (lib "Library") (part "Res-SMD"))
    )
    (comp (ref "R184")
      (value "10K 1%")
      (footprint "RES-SMD-0603")
      (description "0603")
      (fields
        (field (name "MANUFACTURER") "Generic Components")
        (field (name "PUBLISHER") "Altium Hobart Technology Centre")
      )
      (libsource (lib "Library") (part "Res-SMD"))
    )
    (comp (ref "R185")
      (value "10K 1%")
      (footprint "RES-SMD-0603")
      (description "0603")
      (fields
        (field (name "MANUFACTURER") "Generic Components")
        (field (name "PUBLISHER") "Altium Hobart Technology Centre")
      )
      (libsource (lib "Library") (part "Res-SMD"))
    )
    (comp (ref "R186")
      (value "10K 1%")
      (footprint "RES-SMD-0603")
      (description "0603")
      (fields
        (field (name "MANUFACTURER") "Generic Components")
        (field (name "PUBLISHER") "Altium Hobart Technology Centre")
      )
      (libsource (lib "Library") (part "Res-SMD"))
    )
    (comp (ref "R187")
      (value "10K 1%")
      (footprint "RES-SMD-0603")
      (description "0603")
      (fields
        (field (name "MANUFACTURER") "Generic Components")
        (field (name "PUBLISHER") "Altium Hobart Technology Centre")
      )
      (libsource (lib "Library") (part "Res-SMD"))
    )
    (comp (ref "R188")
      (value "10K 1%")
      (footprint "RES-SMD-0603")
      (description "0603")
      (fields
        (field (name "MANUFACTURER") "Generic Components")
        (field (name "PUBLISHER") "Altium Hobart Technology Centre")
      )
      (libsource (lib "Library") (part "Res-SMD"))
    )
    (comp (ref "R189")
      (value "10K 1%")
      (footprint "RES-SMD-0603")
      (description "0603")
      (fields
        (field (name "MANUFACTURER") "Generic Components")
        (field (name "PUBLISHER") "Altium Hobart Technology Centre")
      )
      (libsource (lib "Library") (part "Res-SMD"))
    )
    (comp (ref "R190")
      (value "10K 1%")
      (footprint "RES-SMD-0603")
      (description "0603")
      (fields
        (field (name "MANUFACTURER") "Generic Components")
        (field (name "PUBLISHER") "Altium Hobart Technology Centre")
      )
      (libsource (lib "Library") (part "Res-SMD"))
    )
    (comp (ref "R191")
      (value "10K 1%")
      (footprint "RES-SMD-0603")
      (description "0603")
      (fields
        (field (name "MANUFACTURER") "Generic Components")
        (field (name "PUBLISHER") "Altium Hobart Technology Centre")
      )
      (libsource (lib "Library") (part "Res-SMD"))
    )
    (comp (ref "R192")
      (value "10K 1%")
      (footprint "RES-SMD-0603")
      (description "0603")
      (fields
        (field (name "MANUFACTURER") "Generic Components")
        (field (name "PUBLISHER") "Altium Hobart Technology Centre")
      )
      (libsource (lib "Library") (part "Res-SMD"))
    )
    (comp (ref "R193")
      (value "10K 1%")
      (footprint "RES-SMD-0603")
      (description "0603")
      (fields
        (field (name "MANUFACTURER") "Generic Components")
        (field (name "PUBLISHER") "Altium Hobart Technology Centre")
      )
      (libsource (lib "Library") (part "Res-SMD"))
    )
    (comp (ref "R194")
      (value "10K 1%")
      (footprint "RES-SMD-0603")
      (description "0603")
      (fields
        (field (name "MANUFACTURER") "Generic Components")
        (field (name "PUBLISHER") "Altium Hobart Technology Centre")
      )
      (libsource (lib "Library") (part "Res-SMD"))
    )
    (comp (ref "R195")
      (value "10K 1%")
      (footprint "RES-SMD-0603")
      (description "0603")
      (fields
        (field (name "MANUFACTURER") "Generic Components")
        (field (name "PUBLISHER") "Altium Hobart Technology Centre")
      )
      (libsource (lib "Library") (part "Res-SMD"))
    )
    (comp (ref "R196")
      (value "10K 1%")
      (footprint "RES-SMD-0603")
      (description "0603")
      (fields
        (field (name "MANUFACTURER") "Generic Components")
        (field (name "PUBLISHER") "Altium Hobart Technology Centre")
      )
      (libsource (lib "Library") (part "Res-SMD"))
    )
    (comp (ref "R197")
      (value "10K 1%")
      (footprint "RES-SMD-0603")
      (description "0603")
      (fields
        (field (name "MANUFACTURER") "Generic Components")
        (field (name "PUBLISHER") "Altium Hobart Technology Centre")
      )
      (libsource (lib "Library") (part "Res-SMD"))
    )
    (comp (ref "R198")
      (value "10K 1%")
      (footprint "RES-SMD-0603")
      (description "0603")
      (fields
        (field (name "MANUFACTURER") "Generic Components")
        (field (name "PUBLISHER") "Altium Hobart Technology Centre")
      )
      (libsource (lib "Library") (part "Res-SMD"))
    )
    (comp (ref "R199")
      (value "10K 1%")
      (footprint "RES-SMD-0603")
      (description "0603")
      (fields
        (field (name "MANUFACTURER") "Generic Components")
        (field (name "PUBLISHER") "Altium Hobart Technology Centre")
      )
      (libsource (lib "Library") (part "Res-SMD"))
    )
    (comp (ref "R200")
      (value "10K 1%")
      (footprint "RES-SMD-0603")
      (description "0603")
      (fields
        (field (name "MANUFACTURER") "Generic Components")
        (field (name "PUBLISHER") "Altium Hobart Technology Centre")
      )
      (libsource (lib "Library") (part "Res-SMD"))
    )
    (comp (ref "R201")
      (value "1K 1%")
      (footprint "RES-SMD-0603")
      (description "0603")
      (fields
        (field (name "MANUFACTURER") "Generic Components")
        (field (name "PUBLISHER") "Altium Hobart Technology Centre")
      )
      (libsource (lib "Library") (part "Res-SMD"))
    )
    (comp (ref "R202")
      (value "1K 1%")
      (footprint "RES-SMD-0603")
      (description "0603")
      (fields
        (field (name "MANUFACTURER") "Generic Components")
        (field (name "PUBLISHER") "Altium Hobart Technology Centre")
      )
      (libsource (lib "Library") (part "Res-SMD"))
    )
    (comp (ref "R203")
      (value "1K 1%")
      (footprint "RES-SMD-0603")
      (description "0603")
      (fields
        (field (name "MANUFACTURER") "Generic Components")
        (field (name "PUBLISHER") "Altium Hobart Technology Centre")
      )
      (libsource (lib "Library") (part "Res-SMD"))
    )
    (comp (ref "R204")
      (value "1K 1%")
      (footprint "RES-SMD-0603")
      (description "0603")
      (fields
        (field (name "MANUFACTURER") "Generic Components")
        (field (name "PUBLISHER") "Altium Hobart Technology Centre")
      )
      (libsource (lib "Library") (part "Res-SMD"))
    )
    (comp (ref "R205")
      (value "1K 1%")
      (footprint "RES-SMD-0603")
      (description "0603")
      (fields
        (field (name "MANUFACTURER") "Generic Components")
        (field (name "PUBLISHER") "Altium Hobart Technology Centre")
      )
      (libsource (lib "Library") (part "Res-SMD"))
    )
    (comp (ref "R206")
      (value "1K 1%")
      (footprint "RES-SMD-0603")
      (description "0603")
      (fields
        (field (name "MANUFACTURER") "Generic Components")
        (field (name "PUBLISHER") "Altium Hobart Technology Centre")
      )
      (libsource (lib "Library") (part "Res-SMD"))
    )
    (comp (ref "R207")
      (value "1K 1%")
      (footprint "RES-SMD-0603")
      (description "0603")
      (fields
        (field (name "MANUFACTURER") "Generic Components")
        (field (name "PUBLISHER") "Altium Hobart Technology Centre")
      )
      (libsource (lib "Library") (part "Res-SMD"))
    )
    (comp (ref "R208")
      (value "1K 1%")
      (footprint "RES-SMD-0603")
      (description "0603")
      (fields
        (field (name "MANUFACTURER") "Generic Components")
        (field (name "PUBLISHER") "Altium Hobart Technology Centre")
      )
      (libsource (lib "Library") (part "Res-SMD"))
    )
    (comp (ref "R209")
      (value "1K 1%")
      (footprint "RES-SMD-0603")
      (description "0603")
      (fields
        (field (name "MANUFACTURER") "Generic Components")
        (field (name "PUBLISHER") "Altium Hobart Technology Centre")
      )
      (libsource (lib "Library") (part "Res-SMD"))
    )
    (comp (ref "R210")
      (value "10K 1%")
      (footprint "RES-SMD-0603")
      (description "0603")
      (fields
        (field (name "MANUFACTURER") "Generic Components")
        (field (name "PUBLISHER") "Altium Hobart Technology Centre")
      )
      (libsource (lib "Library") (part "Res-SMD"))
    )
    (comp (ref "R211")
      (value "10K 1%")
      (footprint "RES-SMD-0603")
      (description "0603")
      (fields
        (field (name "MANUFACTURER") "Generic Components")
        (field (name "PUBLISHER") "Altium Hobart Technology Centre")
      )
      (libsource (lib "Library") (part "Res-SMD"))
    )
    (comp (ref "R212")
      (value "10K 1%")
      (footprint "RES-SMD-0603")
      (description "0603")
      (fields
        (field (name "MANUFACTURER") "Generic Components")
        (field (name "PUBLISHER") "Altium Hobart Technology Centre")
      )
      (libsource (lib "Library") (part "Res-SMD"))
    )
    (comp (ref "R213")
      (value "10K 1%")
      (footprint "RES-SMD-0603")
      (description "0603")
      (fields
        (field (name "MANUFACTURER") "Generic Components")
        (field (name "PUBLISHER") "Altium Hobart Technology Centre")
      )
      (libsource (lib "Library") (part "Res-SMD"))
    )
    (comp (ref "R214")
      (value "10K 1%")
      (footprint "RES-SMD-0603")
      (description "0603")
      (fields
        (field (name "MANUFACTURER") "Generic Components")
        (field (name "PUBLISHER") "Altium Hobart Technology Centre")
      )
      (libsource (lib "Library") (part "Res-SMD"))
    )
    (comp (ref "R215")
      (value "10K 1%")
      (footprint "RES-SMD-0603")
      (description "0603")
      (fields
        (field (name "MANUFACTURER") "Generic Components")
        (field (name "PUBLISHER") "Altium Hobart Technology Centre")
      )
      (libsource (lib "Library") (part "Res-SMD"))
    )
    (comp (ref "R216")
      (value "10K 1%")
      (footprint "RES-SMD-0603")
      (description "0603")
      (fields
        (field (name "MANUFACTURER") "Generic Components")
        (field (name "PUBLISHER") "Altium Hobart Technology Centre")
      )
      (libsource (lib "Library") (part "Res-SMD"))
    )
    (comp (ref "R217")
      (value "10K 1%")
      (footprint "RES-SMD-0603")
      (description "0603")
      (fields
        (field (name "MANUFACTURER") "Generic Components")
        (field (name "PUBLISHER") "Altium Hobart Technology Centre")
      )
      (libsource (lib "Library") (part "Res-SMD"))
    )
    (comp (ref "R218")
      (value "10K 1%")
      (footprint "RES-SMD-0603")
      (description "0603")
      (fields
        (field (name "MANUFACTURER") "Generic Components")
        (field (name "PUBLISHER") "Altium Hobart Technology Centre")
      )
      (libsource (lib "Library") (part "Res-SMD"))
    )
    (comp (ref "R219")
      (value "10K 1%")
      (footprint "RES-SMD-0603")
      (description "0603")
      (fields
        (field (name "MANUFACTURER") "Generic Components")
        (field (name "PUBLISHER") "Altium Hobart Technology Centre")
      )
      (libsource (lib "Library") (part "Res-SMD"))
    )
    (comp (ref "R220")
      (value "10K 1%")
      (footprint "RES-SMD-0603")
      (description "0603")
      (fields
        (field (name "MANUFACTURER") "Generic Components")
        (field (name "PUBLISHER") "Altium Hobart Technology Centre")
      )
      (libsource (lib "Library") (part "Res-SMD"))
    )
    (comp (ref "R221")
      (value "10K 1%")
      (footprint "RES-SMD-0603")
      (description "0603")
      (fields
        (field (name "MANUFACTURER") "Generic Components")
        (field (name "PUBLISHER") "Altium Hobart Technology Centre")
      )
      (libsource (lib "Library") (part "Res-SMD"))
    )
    (comp (ref "R222")
      (value "10K 1%")
      (footprint "RES-SMD-0603")
      (description "0603")
      (fields
        (field (name "MANUFACTURER") "Generic Components")
        (field (name "PUBLISHER") "Altium Hobart Technology Centre")
      )
      (libsource (lib "Library") (part "Res-SMD"))
    )
    (comp (ref "R223")
      (value "10K 1%")
      (footprint "RES-SMD-0603")
      (description "0603")
      (fields
        (field (name "MANUFACTURER") "Generic Components")
        (field (name "PUBLISHER") "Altium Hobart Technology Centre")
      )
      (libsource (lib "Library") (part "Res-SMD"))
    )
    (comp (ref "R224")
      (value "10K 1%")
      (footprint "RES-SMD-0603")
      (description "0603")
      (fields
        (field (name "MANUFACTURER") "Generic Components")
        (field (name "PUBLISHER") "Altium Hobart Technology Centre")
      )
      (libsource (lib "Library") (part "Res-SMD"))
    )
    (comp (ref "R225")
      (value "10K 1%")
      (footprint "RES-SMD-0603")
      (description "0603")
      (fields
        (field (name "MANUFACTURER") "Generic Components")
        (field (name "PUBLISHER") "Altium Hobart Technology Centre")
      )
      (libsource (lib "Library") (part "Res-SMD"))
    )
    (comp (ref "R226")
      (value "10K 1%")
      (footprint "RES-SMD-0603")
      (description "0603")
      (fields
        (field (name "MANUFACTURER") "Generic Components")
        (field (name "PUBLISHER") "Altium Hobart Technology Centre")
      )
      (libsource (lib "Library") (part "Res-SMD"))
    )
    (comp (ref "R227")
      (value "10K 1%")
      (footprint "RES-SMD-0603")
      (description "0603")
      (fields
        (field (name "MANUFACTURER") "Generic Components")
        (field (name "PUBLISHER") "Altium Hobart Technology Centre")
      )
      (libsource (lib "Library") (part "Res-SMD"))
    )
    (comp (ref "R228")
      (value "10K 1%")
      (footprint "RES-SMD-0603")
      (description "0603")
      (fields
        (field (name "MANUFACTURER") "Generic Components")
        (field (name "PUBLISHER") "Altium Hobart Technology Centre")
      )
      (libsource (lib "Library") (part "Res-SMD"))
    )
    (comp (ref "R229")
      (value "10K 1%")
      (footprint "RES-SMD-0603")
      (description "0603")
      (fields
        (field (name "MANUFACTURER") "Generic Components")
        (field (name "PUBLISHER") "Altium Hobart Technology Centre")
      )
      (libsource (lib "Library") (part "Res-SMD"))
    )
    (comp (ref "R230")
      (value "10K 1%")
      (footprint "RES-SMD-0603")
      (description "0603")
      (fields
        (field (name "MANUFACTURER") "Generic Components")
        (field (name "PUBLISHER") "Altium Hobart Technology Centre")
      )
      (libsource (lib "Library") (part "Res-SMD"))
    )
    (comp (ref "R231")
      (value "10K 1%")
      (footprint "RES-SMD-0603")
      (description "0603")
      (fields
        (field (name "MANUFACTURER") "Generic Components")
        (field (name "PUBLISHER") "Altium Hobart Technology Centre")
      )
      (libsource (lib "Library") (part "Res-SMD"))
    )
    (comp (ref "R232")
      (value "10K 1%")
      (footprint "RES-SMD-0603")
      (description "0603")
      (fields
        (field (name "MANUFACTURER") "Generic Components")
        (field (name "PUBLISHER") "Altium Hobart Technology Centre")
      )
      (libsource (lib "Library") (part "Res-SMD"))
    )
    (comp (ref "R233")
      (value "10K 1%")
      (footprint "RES-SMD-0603")
      (description "0603")
      (fields
        (field (name "MANUFACTURER") "Generic Components")
        (field (name "PUBLISHER") "Altium Hobart Technology Centre")
      )
      (libsource (lib "Library") (part "Res-SMD"))
    )
    (comp (ref "R234")
      (value "10K 1%")
      (footprint "RES-SMD-0603")
      (description "0603")
      (fields
        (field (name "MANUFACTURER") "Generic Components")
        (field (name "PUBLISHER") "Altium Hobart Technology Centre")
      )
      (libsource (lib "Library") (part "Res-SMD"))
    )
    (comp (ref "R235")
      (value "10K 1%")
      (footprint "RES-SMD-0603")
      (description "0603")
      (fields
        (field (name "MANUFACTURER") "Generic Components")
        (field (name "PUBLISHER") "Altium Hobart Technology Centre")
      )
      (libsource (lib "Library") (part "Res-SMD"))
    )
    (comp (ref "R236")
      (value "10K 1%")
      (footprint "RES-SMD-0603")
      (description "0603")
      (fields
        (field (name "MANUFACTURER") "Generic Components")
        (field (name "PUBLISHER") "Altium Hobart Technology Centre")
      )
      (libsource (lib "Library") (part "Res-SMD"))
    )
    (comp (ref "R237")
      (value "1K 1%")
      (footprint "RES-SMD-0603")
      (description "0603")
      (fields
        (field (name "MANUFACTURER") "Generic Components")
        (field (name "PUBLISHER") "Altium Hobart Technology Centre")
      )
      (libsource (lib "Library") (part "Res-SMD"))
    )
    (comp (ref "R238")
      (value "1K 1%")
      (footprint "RES-SMD-0603")
      (description "0603")
      (fields
        (field (name "MANUFACTURER") "Generic Components")
        (field (name "PUBLISHER") "Altium Hobart Technology Centre")
      )
      (libsource (lib "Library") (part "Res-SMD"))
    )
    (comp (ref "R239")
      (value "1K 1%")
      (footprint "RES-SMD-0603")
      (description "0603")
      (fields
        (field (name "MANUFACTURER") "Generic Components")
        (field (name "PUBLISHER") "Altium Hobart Technology Centre")
      )
      (libsource (lib "Library") (part "Res-SMD"))
    )
    (comp (ref "R240")
      (value "1K 1%")
      (footprint "RES-SMD-0603")
      (description "0603")
      (fields
        (field (name "MANUFACTURER") "Generic Components")
        (field (name "PUBLISHER") "Altium Hobart Technology Centre")
      )
      (libsource (lib "Library") (part "Res-SMD"))
    )
    (comp (ref "R241")
      (value "1K 1%")
      (footprint "RES-SMD-0603")
      (description "0603")
      (fields
        (field (name "MANUFACTURER") "Generic Components")
        (field (name "PUBLISHER") "Altium Hobart Technology Centre")
      )
      (libsource (lib "Library") (part "Res-SMD"))
    )
    (comp (ref "R242")
      (value "1K 1%")
      (footprint "RES-SMD-0603")
      (description "0603")
      (fields
        (field (name "MANUFACTURER") "Generic Components")
        (field (name "PUBLISHER") "Altium Hobart Technology Centre")
      )
      (libsource (lib "Library") (part "Res-SMD"))
    )
    (comp (ref "R243")
      (value "1K 1%")
      (footprint "RES-SMD-0603")
      (description "0603")
      (fields
        (field (name "MANUFACTURER") "Generic Components")
        (field (name "PUBLISHER") "Altium Hobart Technology Centre")
      )
      (libsource (lib "Library") (part "Res-SMD"))
    )
    (comp (ref "R244")
      (value "1K 1%")
      (footprint "RES-SMD-0603")
      (description "0603")
      (fields
        (field (name "MANUFACTURER") "Generic Components")
        (field (name "PUBLISHER") "Altium Hobart Technology Centre")
      )
      (libsource (lib "Library") (part "Res-SMD"))
    )
    (comp (ref "R245")
      (value "1K 1%")
      (footprint "RES-SMD-0603")
      (description "0603")
      (fields
        (field (name "MANUFACTURER") "Generic Components")
        (field (name "PUBLISHER") "Altium Hobart Technology Centre")
      )
      (libsource (lib "Library") (part "Res-SMD"))
    )
    (comp (ref "R246")
      (value "10K 1%")
      (footprint "RES-SMD-0603")
      (description "0603")
      (fields
        (field (name "MANUFACTURER") "Generic Components")
        (field (name "PUBLISHER") "Altium Hobart Technology Centre")
      )
      (libsource (lib "Library") (part "Res-SMD"))
    )
    (comp (ref "R247")
      (value "10K 1%")
      (footprint "RES-SMD-0603")
      (description "0603")
      (fields
        (field (name "MANUFACTURER") "Generic Components")
        (field (name "PUBLISHER") "Altium Hobart Technology Centre")
      )
      (libsource (lib "Library") (part "Res-SMD"))
    )
    (comp (ref "R248")
      (value "10K 1%")
      (footprint "RES-SMD-0603")
      (description "0603")
      (fields
        (field (name "MANUFACTURER") "Generic Components")
        (field (name "PUBLISHER") "Altium Hobart Technology Centre")
      )
      (libsource (lib "Library") (part "Res-SMD"))
    )
    (comp (ref "R249")
      (value "10K 1%")
      (footprint "RES-SMD-0603")
      (description "0603")
      (fields
        (field (name "MANUFACTURER") "Generic Components")
        (field (name "PUBLISHER") "Altium Hobart Technology Centre")
      )
      (libsource (lib "Library") (part "Res-SMD"))
    )
    (comp (ref "R250")
      (value "10K 1%")
      (footprint "RES-SMD-0603")
      (description "0603")
      (fields
        (field (name "MANUFACTURER") "Generic Components")
        (field (name "PUBLISHER") "Altium Hobart Technology Centre")
      )
      (libsource (lib "Library") (part "Res-SMD"))
    )
    (comp (ref "R251")
      (value "10K 1%")
      (footprint "RES-SMD-0603")
      (description "0603")
      (fields
        (field (name "MANUFACTURER") "Generic Components")
        (field (name "PUBLISHER") "Altium Hobart Technology Centre")
      )
      (libsource (lib "Library") (part "Res-SMD"))
    )
    (comp (ref "R252")
      (value "10K 1%")
      (footprint "RES-SMD-0603")
      (description "0603")
      (fields
        (field (name "MANUFACTURER") "Generic Components")
        (field (name "PUBLISHER") "Altium Hobart Technology Centre")
      )
      (libsource (lib "Library") (part "Res-SMD"))
    )
    (comp (ref "R253")
      (value "10K 1%")
      (footprint "RES-SMD-0603")
      (description "0603")
      (fields
        (field (name "MANUFACTURER") "Generic Components")
        (field (name "PUBLISHER") "Altium Hobart Technology Centre")
      )
      (libsource (lib "Library") (part "Res-SMD"))
    )
    (comp (ref "R254")
      (value "10K 1%")
      (footprint "RES-SMD-0603")
      (description "0603")
      (fields
        (field (name "MANUFACTURER") "Generic Components")
        (field (name "PUBLISHER") "Altium Hobart Technology Centre")
      )
      (libsource (lib "Library") (part "Res-SMD"))
    )
    (comp (ref "R255")
      (value "10K 1%")
      (footprint "RES-SMD-0603")
      (description "0603")
      (fields
        (field (name "MANUFACTURER") "Generic Components")
        (field (name "PUBLISHER") "Altium Hobart Technology Centre")
      )
      (libsource (lib "Library") (part "Res-SMD"))
    )
    (comp (ref "R256")
      (value "10K 1%")
      (footprint "RES-SMD-0603")
      (description "0603")
      (fields
        (field (name "MANUFACTURER") "Generic Components")
        (field (name "PUBLISHER") "Altium Hobart Technology Centre")
      )
      (libsource (lib "Library") (part "Res-SMD"))
    )
    (comp (ref "R257")
      (value "10K 1%")
      (footprint "RES-SMD-0603")
      (description "0603")
      (fields
        (field (name "MANUFACTURER") "Generic Components")
        (field (name "PUBLISHER") "Altium Hobart Technology Centre")
      )
      (libsource (lib "Library") (part "Res-SMD"))
    )
    (comp (ref "R258")
      (value "10K 1%")
      (footprint "RES-SMD-0603")
      (description "0603")
      (fields
        (field (name "MANUFACTURER") "Generic Components")
        (field (name "PUBLISHER") "Altium Hobart Technology Centre")
      )
      (libsource (lib "Library") (part "Res-SMD"))
    )
    (comp (ref "R259")
      (value "10K 1%")
      (footprint "RES-SMD-0603")
      (description "0603")
      (fields
        (field (name "MANUFACTURER") "Generic Components")
        (field (name "PUBLISHER") "Altium Hobart Technology Centre")
      )
      (libsource (lib "Library") (part "Res-SMD"))
    )
    (comp (ref "R260")
      (value "10K 1%")
      (footprint "RES-SMD-0603")
      (description "0603")
      (fields
        (field (name "MANUFACTURER") "Generic Components")
        (field (name "PUBLISHER") "Altium Hobart Technology Centre")
      )
      (libsource (lib "Library") (part "Res-SMD"))
    )
    (comp (ref "R261")
      (value "10K 1%")
      (footprint "RES-SMD-0603")
      (description "0603")
      (fields
        (field (name "MANUFACTURER") "Generic Components")
        (field (name "PUBLISHER") "Altium Hobart Technology Centre")
      )
      (libsource (lib "Library") (part "Res-SMD"))
    )
    (comp (ref "R262")
      (value "10K 1%")
      (footprint "RES-SMD-0603")
      (description "0603")
      (fields
        (field (name "MANUFACTURER") "Generic Components")
        (field (name "PUBLISHER") "Altium Hobart Technology Centre")
      )
      (libsource (lib "Library") (part "Res-SMD"))
    )
    (comp (ref "R263")
      (value "10K 1%")
      (footprint "RES-SMD-0603")
      (description "0603")
      (fields
        (field (name "MANUFACTURER") "Generic Components")
        (field (name "PUBLISHER") "Altium Hobart Technology Centre")
      )
      (libsource (lib "Library") (part "Res-SMD"))
    )
    (comp (ref "R264")
      (value "10K 1%")
      (footprint "RES-SMD-0603")
      (description "0603")
      (fields
        (field (name "MANUFACTURER") "Generic Components")
        (field (name "PUBLISHER") "Altium Hobart Technology Centre")
      )
      (libsource (lib "Library") (part "Res-SMD"))
    )
    (comp (ref "R265")
      (value "1K 1%")
      (footprint "RES-SMD-0603")
      (description "0603")
      (fields
        (field (name "MANUFACTURER") "Generic Components")
        (field (name "PUBLISHER") "Altium Hobart Technology Centre")
      )
      (libsource (lib "Library") (part "Res-SMD"))
    )
    (comp (ref "R266")
      (value "1K 1%")
      (footprint "RES-SMD-0603")
      (description "0603")
      (fields
        (field (name "MANUFACTURER") "Generic Components")
        (field (name "PUBLISHER") "Altium Hobart Technology Centre")
      )
      (libsource (lib "Library") (part "Res-SMD"))
    )
    (comp (ref "R267")
      (value "1K 1%")
      (footprint "RES-SMD-0603")
      (description "0603")
      (fields
        (field (name "MANUFACTURER") "Generic Components")
        (field (name "PUBLISHER") "Altium Hobart Technology Centre")
      )
      (libsource (lib "Library") (part "Res-SMD"))
    )
    (comp (ref "R268")
      (value "1K 1%")
      (footprint "RES-SMD-0603")
      (description "0603")
      (fields
        (field (name "MANUFACTURER") "Generic Components")
        (field (name "PUBLISHER") "Altium Hobart Technology Centre")
      )
      (libsource (lib "Library") (part "Res-SMD"))
    )
    (comp (ref "R269")
      (value "1K 1%")
      (footprint "RES-SMD-0603")
      (description "0603")
      (fields
        (field (name "MANUFACTURER") "Generic Components")
        (field (name "PUBLISHER") "Altium Hobart Technology Centre")
      )
      (libsource (lib "Library") (part "Res-SMD"))
    )
    (comp (ref "R270")
      (value "10K 1%")
      (footprint "RES-SMD-0603")
      (description "0603")
      (fields
        (field (name "MANUFACTURER") "Generic Components")
        (field (name "PUBLISHER") "Altium Hobart Technology Centre")
      )
      (libsource (lib "Library") (part "Res-SMD"))
    )
    (comp (ref "R271")
      (value "10K 1%")
      (footprint "RES-SMD-0603")
      (description "0603")
      (fields
        (field (name "MANUFACTURER") "Generic Components")
        (field (name "PUBLISHER") "Altium Hobart Technology Centre")
      )
      (libsource (lib "Library") (part "Res-SMD"))
    )
    (comp (ref "R272")
      (value "10K 1%")
      (footprint "RES-SMD-0603")
      (description "0603")
      (fields
        (field (name "MANUFACTURER") "Generic Components")
        (field (name "PUBLISHER") "Altium Hobart Technology Centre")
      )
      (libsource (lib "Library") (part "Res-SMD"))
    )
    (comp (ref "R273")
      (value "10K 1%")
      (footprint "RES-SMD-0603")
      (description "0603")
      (fields
        (field (name "MANUFACTURER") "Generic Components")
        (field (name "PUBLISHER") "Altium Hobart Technology Centre")
      )
      (libsource (lib "Library") (part "Res-SMD"))
    )
    (comp (ref "R274")
      (value "10K 1%")
      (footprint "RES-SMD-0603")
      (description "0603")
      (fields
        (field (name "MANUFACTURER") "Generic Components")
        (field (name "PUBLISHER") "Altium Hobart Technology Centre")
      )
      (libsource (lib "Library") (part "Res-SMD"))
    )
  )
  (nets
    (net (code "1") (name "+12") (class "Default")
      (node (ref "DIO33") (pin "2") (pinfunction "K_2") (pintype "passive"))
      (node (ref "DIO34") (pin "2") (pinfunction "K_2") (pintype "passive"))
      (node (ref "DIO35") (pin "2") (pinfunction "K_2") (pintype "passive"))
      (node (ref "DIO36") (pin "2") (pinfunction "K_2") (pintype "passive"))
      (node (ref "DIO37") (pin "2") (pinfunction "K_2") (pintype "passive"))
      (node (ref "DIO38") (pin "2") (pinfunction "K_2") (pintype "passive"))
      (node (ref "DIO39") (pin "2") (pinfunction "K_2") (pintype "passive"))
      (node (ref "DIO40") (pin "2") (pinfunction "K_2") (pintype "passive"))
      (node (ref "DIO41") (pin "2") (pinfunction "K_2") (pintype "passive"))
      (node (ref "DIO42") (pin "2") (pinfunction "K_2") (pintype "passive"))
      (node (ref "DIO43") (pin "2") (pinfunction "K_2") (pintype "passive"))
      (node (ref "DIO44") (pin "2") (pinfunction "K_2") (pintype "passive"))
      (node (ref "DIO45") (pin "2") (pinfunction "K_2") (pintype "passive"))
      (node (ref "DIO46") (pin "2") (pinfunction "K_2") (pintype "passive"))
      (node (ref "DIO47") (pin "2") (pinfunction "K_2") (pintype "passive"))
      (node (ref "DIO48") (pin "2") (pinfunction "K_2") (pintype "passive"))
      (node (ref "DIO49") (pin "2") (pinfunction "K_2") (pintype "passive"))
      (node (ref "DIO50") (pin "2") (pinfunction "K_2") (pintype "passive"))
      (node (ref "DIO51") (pin "2") (pinfunction "K_2") (pintype "passive"))
      (node (ref "DIO52") (pin "2") (pinfunction "K_2") (pintype "passive"))
      (node (ref "DIO53") (pin "2") (pinfunction "K_2") (pintype "passive"))
      (node (ref "DIO54") (pin "2") (pinfunction "K_2") (pintype "passive"))
      (node (ref "DIO55") (pin "2") (pinfunction "K_2") (pintype "passive"))
      (node (ref "DIO56") (pin "2") (pinfunction "K_2") (pintype "passive"))
      (node (ref "DIO57") (pin "2") (pinfunction "K_2") (pintype "passive"))
      (node (ref "DIO58") (pin "2") (pinfunction "K_2") (pintype "passive"))
      (node (ref "DIO59") (pin "2") (pinfunction "K_2") (pintype "passive"))
      (node (ref "DIO60") (pin "2") (pinfunction "K_2") (pintype "passive"))
      (node (ref "DIO61") (pin "2") (pinfunction "K_2") (pintype "passive"))
      (node (ref "DIO62") (pin "2") (pinfunction "K_2") (pintype "passive"))
      (node (ref "DIO63") (pin "2") (pinfunction "K_2") (pintype "passive"))
      (node (ref "DIO64") (pin "2") (pinfunction "K_2") (pintype "passive"))
      (node (ref "LD33") (pin "1") (pinfunction "1_1") (pintype "passive"))
      (node (ref "LD34") (pin "1") (pinfunction "1_1") (pintype "passive"))
      (node (ref "LD35") (pin "1") (pinfunction "1_1") (pintype "passive"))
      (node (ref "LD36") (pin "1") (pinfunction "1_1") (pintype "passive"))
      (node (ref "LD37") (pin "1") (pinfunction "1_1") (pintype "passive"))
      (node (ref "LD38") (pin "1") (pinfunction "1_1") (pintype "passive"))
      (node (ref "LD39") (pin "1") (pinfunction "1_1") (pintype "passive"))
      (node (ref "LD40") (pin "1") (pinfunction "1_1") (pintype "passive"))
      (node (ref "LD41") (pin "1") (pinfunction "1_1") (pintype "passive"))
      (node (ref "LD42") (pin "1") (pinfunction "1_1") (pintype "passive"))
      (node (ref "LD43") (pin "1") (pinfunction "1_1") (pintype "passive"))
      (node (ref "LD44") (pin "1") (pinfunction "1_1") (pintype "passive"))
      (node (ref "LD45") (pin "1") (pinfunction "1_1") (pintype "passive"))
      (node (ref "LD46") (pin "1") (pinfunction "1_1") (pintype "passive"))
      (node (ref "LD47") (pin "1") (pinfunction "1_1") (pintype "passive"))
      (node (ref "LD48") (pin "1") (pinfunction "1_1") (pintype "passive"))
      (node (ref "LD49") (pin "1") (pinfunction "1_1") (pintype "passive"))
      (node (ref "LD50") (pin "1") (pinfunction "1_1") (pintype "passive"))
      (node (ref "LD51") (pin "1") (pinfunction "1_1") (pintype "passive"))
      (node (ref "LD52") (pin "1") (pinfunction "1_1") (pintype "passive"))
      (node (ref "LD53") (pin "1") (pinfunction "1_1") (pintype "passive"))
      (node (ref "LD54") (pin "1") (pinfunction "1_1") (pintype "passive"))
      (node (ref "LD55") (pin "1") (pinfunction "1_1") (pintype "passive"))
      (node (ref "LD56") (pin "1") (pinfunction "1_1") (pintype "passive"))
      (node (ref "LD57") (pin "1") (pinfunction "1_1") (pintype "passive"))
      (node (ref "LD58") (pin "1") (pinfunction "1_1") (pintype "passive"))
      (node (ref "LD59") (pin "1") (pinfunction "1_1") (pintype "passive"))
      (node (ref "LD60") (pin "1") (pinfunction "1_1") (pintype "passive"))
      (node (ref "LD61") (pin "1") (pinfunction "1_1") (pintype "passive"))
      (node (ref "LD62") (pin "1") (pinfunction "1_1") (pintype "passive"))
      (node (ref "LD63") (pin "1") (pinfunction "1_1") (pintype "passive"))
      (node (ref "LD64") (pin "1") (pinfunction "1_1") (pintype "passive"))
      (node (ref "R147") (pin "1") (pinfunction "1_1") (pintype "passive"))
      (node (ref "R148") (pin "1") (pinfunction "1_1") (pintype "passive"))
      (node (ref "R149") (pin "1") (pinfunction "1_1") (pintype "passive"))
      (node (ref "R150") (pin "1") (pinfunction "1_1") (pintype "passive"))
      (node (ref "R151") (pin "1") (pinfunction "1_1") (pintype "passive"))
      (node (ref "R152") (pin "1") (pinfunction "1_1") (pintype "passive"))
      (node (ref "R153") (pin "1") (pinfunction "1_1") (pintype "passive"))
      (node (ref "R154") (pin "1") (pinfunction "1_1") (pintype "passive"))
      (node (ref "R155") (pin "1") (pinfunction "1_1") (pintype "passive"))
      (node (ref "R183") (pin "1") (pinfunction "1_1") (pintype "passive"))
      (node (ref "R184") (pin "1") (pinfunction "1_1") (pintype "passive"))
      (node (ref "R185") (pin "1") (pinfunction "1_1") (pintype "passive"))
      (node (ref "R186") (pin "1") (pinfunction "1_1") (pintype "passive"))
      (node (ref "R187") (pin "1") (pinfunction "1_1") (pintype "passive"))
      (node (ref "R188") (pin "1") (pinfunction "1_1") (pintype "passive"))
      (node (ref "R189") (pin "1") (pinfunction "1_1") (pintype "passive"))
      (node (ref "R190") (pin "1") (pinfunction "1_1") (pintype "passive"))
      (node (ref "R191") (pin "1") (pinfunction "1_1") (pintype "passive"))
      (node (ref "R219") (pin "1") (pinfunction "1_1") (pintype "passive"))
      (node (ref "R220") (pin "1") (pinfunction "1_1") (pintype "passive"))
      (node (ref "R221") (pin "1") (pinfunction "1_1") (pintype "passive"))
      (node (ref "R222") (pin "1") (pinfunction "1_1") (pintype "passive"))
      (node (ref "R223") (pin "1") (pinfunction "1_1") (pintype "passive"))
      (node (ref "R224") (pin "1") (pinfunction "1_1") (pintype "passive"))
      (node (ref "R225") (pin "1") (pinfunction "1_1") (pintype "passive"))
      (node (ref "R226") (pin "1") (pinfunction "1_1") (pintype "passive"))
      (node (ref "R227") (pin "1") (pinfunction "1_1") (pintype "passive"))
      (node (ref "R255") (pin "1") (pinfunction "1_1") (pintype "passive"))
      (node (ref "R256") (pin "1") (pinfunction "1_1") (pintype "passive"))
      (node (ref "R257") (pin "1") (pinfunction "1_1") (pintype "passive"))
      (node (ref "R258") (pin "1") (pinfunction "1_1") (pintype "passive"))
      (node (ref "R259") (pin "1") (pinfunction "1_1") (pintype "passive"))
    )
    (net (code "2") (name "/SW32") (class "Default")
      (node (ref "R165") (pin "1") (pinfunction "1_1") (pintype "passive"))
    )
    (net (code "3") (name "/SW33") (class "Default")
      (node (ref "R166") (pin "1") (pinfunction "1_1") (pintype "passive"))
    )
    (net (code "4") (name "/SW34") (class "Default")
      (node (ref "R167") (pin "1") (pinfunction "1_1") (pintype "passive"))
    )
    (net (code "5") (name "/SW35") (class "Default")
      (node (ref "R168") (pin "1") (pinfunction "1_1") (pintype "passive"))
    )
    (net (code "6") (name "/SW36") (class "Default")
      (node (ref "R169") (pin "1") (pinfunction "1_1") (pintype "passive"))
    )
    (net (code "7") (name "/SW37") (class "Default")
      (node (ref "R170") (pin "1") (pinfunction "1_1") (pintype "passive"))
    )
    (net (code "8") (name "/SW38") (class "Default")
      (node (ref "R171") (pin "1") (pinfunction "1_1") (pintype "passive"))
    )
    (net (code "9") (name "/SW39") (class "Default")
      (node (ref "R172") (pin "1") (pinfunction "1_1") (pintype "passive"))
    )
    (net (code "10") (name "/SW40") (class "Default")
      (node (ref "R173") (pin "1") (pinfunction "1_1") (pintype "passive"))
    )
    (net (code "11") (name "/SW41") (class "Default")
      (node (ref "R201") (pin "1") (pinfunction "1_1") (pintype "passive"))
    )
    (net (code "12") (name "/SW42") (class "Default")
      (node (ref "R202") (pin "1") (pinfunction "1_1") (pintype "passive"))
    )
    (net (code "13") (name "/SW43") (class "Default")
      (node (ref "R203") (pin "1") (pinfunction "1_1") (pintype "passive"))
    )
    (net (code "14") (name "/SW44") (class "Default")
      (node (ref "R204") (pin "1") (pinfunction "1_1") (pintype "passive"))
    )
    (net (code "15") (name "/SW45") (class "Default")
      (node (ref "R205") (pin "1") (pinfunction "1_1") (pintype "passive"))
    )
    (net (code "16") (name "/SW46") (class "Default")
      (node (ref "R206") (pin "1") (pinfunction "1_1") (pintype "passive"))
    )
    (net (code "17") (name "/SW47") (class "Default")
      (node (ref "R207") (pin "1") (pinfunction "1_1") (pintype "passive"))
    )
    (net (code "18") (name "/SW48") (class "Default")
      (node (ref "R208") (pin "1") (pinfunction "1_1") (pintype "passive"))
    )
    (net (code "19") (name "/SW49") (class "Default")
      (node (ref "R209") (pin "1") (pinfunction "1_1") (pintype "passive"))
    )
    (net (code "20") (name "/SW50") (class "Default")
      (node (ref "R237") (pin "1") (pinfunction "1_1") (pintype "passive"))
    )
    (net (code "21") (name "/SW51") (class "Default")
      (node (ref "R238") (pin "1") (pinfunction "1_1") (pintype "passive"))
    )
    (net (code "22") (name "/SW52") (class "Default")
      (node (ref "R239") (pin "1") (pinfunction "1_1") (pintype "passive"))
    )
    (net (code "23") (name "/SW53") (class "Default")
      (node (ref "R240") (pin "1") (pinfunction "1_1") (pintype "passive"))
    )
    (net (code "24") (name "/SW54") (class "Default")
      (node (ref "R241") (pin "1") (pinfunction "1_1") (pintype "passive"))
    )
    (net (code "25") (name "/SW55") (class "Default")
      (node (ref "R242") (pin "1") (pinfunction "1_1") (pintype "passive"))
    )
    (net (code "26") (name "/SW56") (class "Default")
      (node (ref "R243") (pin "1") (pinfunction "1_1") (pintype "passive"))
    )
    (net (code "27") (name "/SW57") (class "Default")
      (node (ref "R244") (pin "1") (pinfunction "1_1") (pintype "passive"))
    )
    (net (code "28") (name "/SW58") (class "Default")
      (node (ref "R245") (pin "1") (pinfunction "1_1") (pintype "passive"))
    )
    (net (code "29") (name "/SW59") (class "Default")
      (node (ref "R265") (pin "1") (pinfunction "1_1") (pintype "passive"))
    )
    (net (code "30") (name "/SW60") (class "Default")
      (node (ref "R266") (pin "1") (pinfunction "1_1") (pintype "passive"))
    )
    (net (code "31") (name "/SW61") (class "Default")
      (node (ref "R267") (pin "1") (pinfunction "1_1") (pintype "passive"))
    )
    (net (code "32") (name "/SW62") (class "Default")
      (node (ref "R268") (pin "1") (pinfunction "1_1") (pintype "passive"))
    )
    (net (code "33") (name "/SW63") (class "Default")
      (node (ref "R269") (pin "1") (pinfunction "1_1") (pintype "passive"))
    )
    (net (code "34") (name "GND_AUX") (class "Default")
      (node (ref "Q100") (pin "2") (pinfunction "E_2") (pintype "passive"))
      (node (ref "Q101") (pin "2") (pinfunction "E_2") (pintype "passive"))
      (node (ref "Q111") (pin "2") (pinfunction "E_2") (pintype "passive"))
      (node (ref "Q112") (pin "2") (pinfunction "E_2") (pintype "passive"))
      (node (ref "Q113") (pin "2") (pinfunction "E_2") (pintype "passive"))
      (node (ref "Q114") (pin "2") (pinfunction "E_2") (pintype "passive"))
      (node (ref "Q115") (pin "2") (pinfunction "E_2") (pintype "passive"))
      (node (ref "Q116") (pin "2") (pinfunction "E_2") (pintype "passive"))
      (node (ref "Q117") (pin "2") (pinfunction "E_2") (pintype "passive"))
      (node (ref "Q118") (pin "2") (pinfunction "E_2") (pintype "passive"))
      (node (ref "Q119") (pin "2") (pinfunction "E_2") (pintype "passive"))
      (node (ref "Q125") (pin "2") (pinfunction "E_2") (pintype "passive"))
      (node (ref "Q126") (pin "2") (pinfunction "E_2") (pintype "passive"))
      (node (ref "Q127") (pin "2") (pinfunction "E_2") (pintype "passive"))
      (node (ref "Q128") (pin "2") (pinfunction "E_2") (pintype "passive"))
      (node (ref "Q129") (pin "2") (pinfunction "E_2") (pintype "passive"))
      (node (ref "Q75") (pin "2") (pinfunction "E_2") (pintype "passive"))
      (node (ref "Q76") (pin "2") (pinfunction "E_2") (pintype "passive"))
      (node (ref "Q77") (pin "2") (pinfunction "E_2") (pintype "passive"))
      (node (ref "Q78") (pin "2") (pinfunction "E_2") (pintype "passive"))
      (node (ref "Q79") (pin "2") (pinfunction "E_2") (pintype "passive"))
      (node (ref "Q80") (pin "2") (pinfunction "E_2") (pintype "passive"))
      (node (ref "Q81") (pin "2") (pinfunction "E_2") (pintype "passive"))
      (node (ref "Q82") (pin "2") (pinfunction "E_2") (pintype "passive"))
      (node (ref "Q83") (pin "2") (pinfunction "E_2") (pintype "passive"))
      (node (ref "Q93") (pin "2") (pinfunction "E_2") (pintype "passive"))
      (node (ref "Q94") (pin "2") (pinfunction "E_2") (pintype "passive"))
      (node (ref "Q95") (pin "2") (pinfunction "E_2") (pintype "passive"))
      (node (ref "Q96") (pin "2") (pinfunction "E_2") (pintype "passive"))
      (node (ref "Q97") (pin "2") (pinfunction "E_2") (pintype "passive"))
      (node (ref "Q98") (pin "2") (pinfunction "E_2") (pintype "passive"))
      (node (ref "Q99") (pin "2") (pinfunction "E_2") (pintype "passive"))
      (node (ref "R174") (pin "2") (pinfunction "2_2") (pintype "passive"))
      (node (ref "R175") (pin "2") (pinfunction "2_2") (pintype "passive"))
      (node (ref "R176") (pin "2") (pinfunction "2_2") (pintype "passive"))
      (node (ref "R177") (pin "2") (pinfunction "2_2") (pintype "passive"))
      (node (ref "R178") (pin "2") (pinfunction "2_2") (pintype "passive"))
      (node (ref "R179") (pin "2") (pinfunction "2_2") (pintype "passive"))
      (node (ref "R180") (pin "2") (pinfunction "2_2") (pintype "passive"))
      (node (ref "R181") (pin "2") (pinfunction "2_2") (pintype "passive"))
      (node (ref "R182") (pin "2") (pinfunction "2_2") (pintype "passive"))
      (node (ref "R210") (pin "2") (pinfunction "2_2") (pintype "passive"))
      (node (ref "R211") (pin "2") (pinfunction "2_2") (pintype "passive"))
      (node (ref "R212") (pin "2") (pinfunction "2_2") (pintype "passive"))
      (node (ref "R213") (pin "2") (pinfunction "2_2") (pintype "passive"))
      (node (ref "R214") (pin "2") (pinfunction "2_2") (pintype "passive"))
      (node (ref "R215") (pin "2") (pinfunction "2_2") (pintype "passive"))
      (node (ref "R216") (pin "2") (pinfunction "2_2") (pintype "passive"))
      (node (ref "R217") (pin "2") (pinfunction "2_2") (pintype "passive"))
      (node (ref "R218") (pin "2") (pinfunction "2_2") (pintype "passive"))
      (node (ref "R246") (pin "2") (pinfunction "2_2") (pintype "passive"))
      (node (ref "R247") (pin "2") (pinfunction "2_2") (pintype "passive"))
      (node (ref "R248") (pin "2") (pinfunction "2_2") (pintype "passive"))
      (node (ref "R249") (pin "2") (pinfunction "2_2") (pintype "passive"))
      (node (ref "R250") (pin "2") (pinfunction "2_2") (pintype "passive"))
      (node (ref "R251") (pin "2") (pinfunction "2_2") (pintype "passive"))
      (node (ref "R252") (pin "2") (pinfunction "2_2") (pintype "passive"))
      (node (ref "R253") (pin "2") (pinfunction "2_2") (pintype "passive"))
      (node (ref "R254") (pin "2") (pinfunction "2_2") (pintype "passive"))
      (node (ref "R270") (pin "2") (pinfunction "2_2") (pintype "passive"))
      (node (ref "R271") (pin "2") (pinfunction "2_2") (pintype "passive"))
      (node (ref "R272") (pin "2") (pinfunction "2_2") (pintype "passive"))
      (node (ref "R273") (pin "2") (pinfunction "2_2") (pintype "passive"))
      (node (ref "R274") (pin "2") (pinfunction "2_2") (pintype "passive"))
    )
    (net (code "35") (name "I_LD") (class "Default")
      (node (ref "Q102") (pin "2") (pintype "power_in"))
      (node (ref "Q103") (pin "2") (pintype "power_in"))
      (node (ref "Q104") (pin "2") (pintype "power_in"))
      (node (ref "Q105") (pin "2") (pintype "power_in"))
      (node (ref "Q106") (pin "2") (pintype "power_in"))
      (node (ref "Q107") (pin "2") (pintype "power_in"))
      (node (ref "Q108") (pin "2") (pintype "power_in"))
      (node (ref "Q109") (pin "2") (pintype "power_in"))
      (node (ref "Q110") (pin "2") (pintype "power_in"))
      (node (ref "Q120") (pin "2") (pintype "power_in"))
      (node (ref "Q121") (pin "2") (pintype "power_in"))
      (node (ref "Q122") (pin "2") (pintype "power_in"))
      (node (ref "Q123") (pin "2") (pintype "power_in"))
      (node (ref "Q124") (pin "2") (pintype "power_in"))
      (node (ref "Q56") (pin "2") (pintype "power_in"))
      (node (ref "Q62") (pin "2") (pintype "power_in"))
      (node (ref "Q68") (pin "2") (pintype "power_in"))
      (node (ref "Q69") (pin "2") (pintype "power_in"))
      (node (ref "Q70") (pin "2") (pintype "power_in"))
      (node (ref "Q71") (pin "2") (pintype "power_in"))
      (node (ref "Q72") (pin "2") (pintype "power_in"))
      (node (ref "Q73") (pin "2") (pintype "power_in"))
      (node (ref "Q74") (pin "2") (pintype "power_in"))
      (node (ref "Q84") (pin "2") (pintype "power_in"))
      (node (ref "Q85") (pin "2") (pintype "power_in"))
      (node (ref "Q86") (pin "2") (pintype "power_in"))
      (node (ref "Q87") (pin "2") (pintype "power_in"))
      (node (ref "Q88") (pin "2") (pintype "power_in"))
      (node (ref "Q89") (pin "2") (pintype "power_in"))
      (node (ref "Q90") (pin "2") (pintype "power_in"))
      (node (ref "Q91") (pin "2") (pintype "power_in"))
      (node (ref "Q92") (pin "2") (pintype "power_in"))
    )
    (net (code "36") (name "Net-(DIO33-A)") (class "Default")
      (node (ref "DIO33") (pin "1") (pinfunction "A_1") (pintype "passive"))
      (node (ref "LD33") (pin "3") (pinfunction "3_3") (pintype "passive"))
      (node (ref "Q56") (pin "3") (pintype "power_in"))
    )
    (net (code "37") (name "Net-(DIO34-A)") (class "Default")
      (node (ref "DIO34") (pin "1") (pinfunction "A_1") (pintype "passive"))
      (node (ref "LD34") (pin "3") (pinfunction "3_3") (pintype "passive"))
      (node (ref "Q62") (pin "3") (pintype "power_in"))
    )
    (net (code "38") (name "Net-(DIO35-A)") (class "Default")
      (node (ref "DIO35") (pin "1") (pinfunction "A_1") (pintype "passive"))
      (node (ref "LD35") (pin "3") (pinfunction "3_3") (pintype "passive"))
      (node (ref "Q68") (pin "3") (pintype "power_in"))
    )
    (net (code "39") (name "Net-(DIO36-A)") (class "Default")
      (node (ref "DIO36") (pin "1") (pinfunction "A_1") (pintype "passive"))
      (node (ref "LD37") (pin "3") (pinfunction "3_3") (pintype "passive"))
      (node (ref "Q70") (pin "3") (pintype "power_in"))
    )
    (net (code "40") (name "Net-(DIO37-A)") (class "Default")
      (node (ref "DIO37") (pin "1") (pinfunction "A_1") (pintype "passive"))
      (node (ref "LD40") (pin "3") (pinfunction "3_3") (pintype "passive"))
      (node (ref "Q73") (pin "3") (pintype "power_in"))
    )
    (net (code "41") (name "Net-(DIO38-A)") (class "Default")
      (node (ref "DIO38") (pin "1") (pinfunction "A_1") (pintype "passive"))
      (node (ref "LD36") (pin "3") (pinfunction "3_3") (pintype "passive"))
      (node (ref "Q69") (pin "3") (pintype "power_in"))
    )
    (net (code "42") (name "Net-(DIO39-A)") (class "Default")
      (node (ref "DIO39") (pin "1") (pinfunction "A_1") (pintype "passive"))
      (node (ref "LD38") (pin "3") (pinfunction "3_3") (pintype "passive"))
      (node (ref "Q71") (pin "3") (pintype "power_in"))
    )
    (net (code "43") (name "Net-(DIO40-A)") (class "Default")
      (node (ref "DIO40") (pin "1") (pinfunction "A_1") (pintype "passive"))
      (node (ref "LD39") (pin "3") (pinfunction "3_3") (pintype "passive"))
      (node (ref "Q72") (pin "3") (pintype "power_in"))
    )
    (net (code "44") (name "Net-(DIO41-A)") (class "Default")
      (node (ref "DIO41") (pin "1") (pinfunction "A_1") (pintype "passive"))
      (node (ref "LD41") (pin "3") (pinfunction "3_3") (pintype "passive"))
      (node (ref "Q74") (pin "3") (pintype "power_in"))
    )
    (net (code "45") (name "Net-(DIO42-A)") (class "Default")
      (node (ref "DIO42") (pin "1") (pinfunction "A_1") (pintype "passive"))
      (node (ref "LD42") (pin "3") (pinfunction "3_3") (pintype "passive"))
      (node (ref "Q84") (pin "3") (pintype "power_in"))
    )
    (net (code "46") (name "Net-(DIO43-A)") (class "Default")
      (node (ref "DIO43") (pin "1") (pinfunction "A_1") (pintype "passive"))
      (node (ref "LD43") (pin "3") (pinfunction "3_3") (pintype "passive"))
      (node (ref "Q85") (pin "3") (pintype "power_in"))
    )
    (net (code "47") (name "Net-(DIO44-A)") (class "Default")
      (node (ref "DIO44") (pin "1") (pinfunction "A_1") (pintype "passive"))
      (node (ref "LD45") (pin "3") (pinfunction "3_3") (pintype "passive"))
      (node (ref "Q87") (pin "3") (pintype "power_in"))
    )
    (net (code "48") (name "Net-(DIO45-A)") (class "Default")
      (node (ref "DIO45") (pin "1") (pinfunction "A_1") (pintype "passive"))
      (node (ref "LD46") (pin "3") (pinfunction "3_3") (pintype "passive"))
      (node (ref "Q88") (pin "3") (pintype "power_in"))
    )
    (net (code "49") (name "Net-(DIO46-A)") (class "Default")
      (node (ref "DIO46") (pin "1") (pinfunction "A_1") (pintype "passive"))
      (node (ref "LD44") (pin "3") (pinfunction "3_3") (pintype "passive"))
      (node (ref "Q86") (pin "3") (pintype "power_in"))
    )
    (net (code "50") (name "Net-(DIO47-A)") (class "Default")
      (node (ref "DIO47") (pin "1") (pinfunction "A_1") (pintype "passive"))
      (node (ref "LD47") (pin "3") (pinfunction "3_3") (pintype "passive"))
      (node (ref "Q89") (pin "3") (pintype "power_in"))
    )
    (net (code "51") (name "Net-(DIO48-A)") (class "Default")
      (node (ref "DIO48") (pin "1") (pinfunction "A_1") (pintype "passive"))
      (node (ref "LD48") (pin "3") (pinfunction "3_3") (pintype "passive"))
      (node (ref "Q90") (pin "3") (pintype "power_in"))
    )
    (net (code "52") (name "Net-(DIO49-A)") (class "Default")
      (node (ref "DIO49") (pin "1") (pinfunction "A_1") (pintype "passive"))
      (node (ref "LD49") (pin "3") (pinfunction "3_3") (pintype "passive"))
      (node (ref "Q91") (pin "3") (pintype "power_in"))
    )
    (net (code "53") (name "Net-(DIO50-A)") (class "Default")
      (node (ref "DIO50") (pin "1") (pinfunction "A_1") (pintype "passive"))
      (node (ref "LD50") (pin "3") (pinfunction "3_3") (pintype "passive"))
      (node (ref "Q92") (pin "3") (pintype "power_in"))
    )
    (net (code "54") (name "Net-(DIO51-A)") (class "Default")
      (node (ref "DIO51") (pin "1") (pinfunction "A_1") (pintype "passive"))
      (node (ref "LD53") (pin "3") (pinfunction "3_3") (pintype "passive"))
      (node (ref "Q104") (pin "3") (pintype "power_in"))
    )
    (net (code "55") (name "Net-(DIO52-A)") (class "Default")
      (node (ref "DIO52") (pin "1") (pinfunction "A_1") (pintype "passive"))
      (node (ref "LD51") (pin "3") (pinfunction "3_3") (pintype "passive"))
      (node (ref "Q102") (pin "3") (pintype "power_in"))
    )
    (net (code "56") (name "Net-(DIO53-A)") (class "Default")
      (node (ref "DIO53") (pin "1") (pinfunction "A_1") (pintype "passive"))
      (node (ref "LD52") (pin "3") (pinfunction "3_3") (pintype "passive"))
      (node (ref "Q103") (pin "3") (pintype "power_in"))
    )
    (net (code "57") (name "Net-(DIO54-A)") (class "Default")
      (node (ref "DIO54") (pin "1") (pinfunction "A_1") (pintype "passive"))
      (node (ref "LD54") (pin "3") (pinfunction "3_3") (pintype "passive"))
      (node (ref "Q105") (pin "3") (pintype "power_in"))
    )
    (net (code "58") (name "Net-(DIO55-A)") (class "Default")
      (node (ref "DIO55") (pin "1") (pinfunction "A_1") (pintype "passive"))
      (node (ref "LD55") (pin "3") (pinfunction "3_3") (pintype "passive"))
      (node (ref "Q106") (pin "3") (pintype "power_in"))
    )
    (net (code "59") (name "Net-(DIO56-A)") (class "Default")
      (node (ref "DIO56") (pin "1") (pinfunction "A_1") (pintype "passive"))
      (node (ref "LD56") (pin "3") (pinfunction "3_3") (pintype "passive"))
      (node (ref "Q107") (pin "3") (pintype "power_in"))
    )
    (net (code "60") (name "Net-(DIO57-A)") (class "Default")
      (node (ref "DIO57") (pin "1") (pinfunction "A_1") (pintype "passive"))
      (node (ref "LD57") (pin "3") (pinfunction "3_3") (pintype "passive"))
      (node (ref "Q108") (pin "3") (pintype "power_in"))
    )
    (net (code "61") (name "Net-(DIO58-A)") (class "Default")
      (node (ref "DIO58") (pin "1") (pinfunction "A_1") (pintype "passive"))
      (node (ref "LD58") (pin "3") (pinfunction "3_3") (pintype "passive"))
      (node (ref "Q109") (pin "3") (pintype "power_in"))
    )
    (net (code "62") (name "Net-(DIO59-A)") (class "Default")
      (node (ref "DIO59") (pin "1") (pinfunction "A_1") (pintype "passive"))
      (node (ref "LD59") (pin "3") (pinfunction "3_3") (pintype "passive"))
      (node (ref "Q110") (pin "3") (pintype "power_in"))
    )
    (net (code "63") (name "Net-(DIO60-A)") (class "Default")
      (node (ref "DIO60") (pin "1") (pinfunction "A_1") (pintype "passive"))
      (node (ref "LD60") (pin "3") (pinfunction "3_3") (pintype "passive"))
      (node (ref "Q120") (pin "3") (pintype "power_in"))
    )
    (net (code "64") (name "Net-(DIO61-A)") (class "Default")
      (node (ref "DIO61") (pin "1") (pinfunction "A_1") (pintype "passive"))
      (node (ref "LD61") (pin "3") (pinfunction "3_3") (pintype "passive"))
      (node (ref "Q121") (pin "3") (pintype "power_in"))
    )
    (net (code "65") (name "Net-(DIO62-A)") (class "Default")
      (node (ref "DIO62") (pin "1") (pinfunction "A_1") (pintype "passive"))
      (node (ref "LD62") (pin "3") (pinfunction "3_3") (pintype "passive"))
      (node (ref "Q122") (pin "3") (pintype "power_in"))
    )
    (net (code "66") (name "Net-(DIO63-A)") (class "Default")
      (node (ref "DIO63") (pin "1") (pinfunction "A_1") (pintype "passive"))
      (node (ref "LD63") (pin "3") (pinfunction "3_3") (pintype "passive"))
      (node (ref "Q123") (pin "3") (pintype "power_in"))
    )
    (net (code "67") (name "Net-(DIO64-A)") (class "Default")
      (node (ref "DIO64") (pin "1") (pinfunction "A_1") (pintype "passive"))
      (node (ref "LD64") (pin "3") (pinfunction "3_3") (pintype "passive"))
      (node (ref "Q124") (pin "3") (pintype "power_in"))
    )
    (net (code "68") (name "Net-(Q56-Pad1)") (class "Default")
      (node (ref "Q56") (pin "1") (pintype "power_in"))
      (node (ref "R147") (pin "2") (pinfunction "2_2") (pintype "passive"))
      (node (ref "R156") (pin "2") (pinfunction "2_2") (pintype "passive"))
    )
    (net (code "69") (name "Net-(Q62-Pad1)") (class "Default")
      (node (ref "Q62") (pin "1") (pintype "power_in"))
      (node (ref "R152") (pin "2") (pinfunction "2_2") (pintype "passive"))
      (node (ref "R157") (pin "2") (pinfunction "2_2") (pintype "passive"))
    )
    (net (code "70") (name "Net-(Q68-Pad1)") (class "Default")
      (node (ref "Q68") (pin "1") (pintype "power_in"))
      (node (ref "R148") (pin "2") (pinfunction "2_2") (pintype "passive"))
      (node (ref "R158") (pin "2") (pinfunction "2_2") (pintype "passive"))
    )
    (net (code "71") (name "Net-(Q69-Pad1)") (class "Default")
      (node (ref "Q69") (pin "1") (pintype "power_in"))
      (node (ref "R153") (pin "2") (pinfunction "2_2") (pintype "passive"))
      (node (ref "R159") (pin "2") (pinfunction "2_2") (pintype "passive"))
    )
    (net (code "72") (name "Net-(Q70-Pad1)") (class "Default")
      (node (ref "Q70") (pin "1") (pintype "power_in"))
      (node (ref "R151") (pin "2") (pinfunction "2_2") (pintype "passive"))
      (node (ref "R160") (pin "2") (pinfunction "2_2") (pintype "passive"))
    )
    (net (code "73") (name "Net-(Q71-Pad1)") (class "Default")
      (node (ref "Q71") (pin "1") (pintype "power_in"))
      (node (ref "R149") (pin "2") (pinfunction "2_2") (pintype "passive"))
      (node (ref "R161") (pin "2") (pinfunction "2_2") (pintype "passive"))
    )
    (net (code "74") (name "Net-(Q72-Pad1)") (class "Default")
      (node (ref "Q72") (pin "1") (pintype "power_in"))
      (node (ref "R154") (pin "2") (pinfunction "2_2") (pintype "passive"))
      (node (ref "R162") (pin "2") (pinfunction "2_2") (pintype "passive"))
    )
    (net (code "75") (name "Net-(Q73-Pad1)") (class "Default")
      (node (ref "Q73") (pin "1") (pintype "power_in"))
      (node (ref "R150") (pin "2") (pinfunction "2_2") (pintype "passive"))
      (node (ref "R163") (pin "2") (pinfunction "2_2") (pintype "passive"))
    )
    (net (code "76") (name "Net-(Q74-Pad1)") (class "Default")
      (node (ref "Q74") (pin "1") (pintype "power_in"))
      (node (ref "R155") (pin "2") (pinfunction "2_2") (pintype "passive"))
      (node (ref "R164") (pin "2") (pinfunction "2_2") (pintype "passive"))
    )
    (net (code "77") (name "Net-(Q75-B)") (class "Default")
      (node (ref "Q75") (pin "1") (pinfunction "B_1") (pintype "passive"))
      (node (ref "R165") (pin "2") (pinfunction "2_2") (pintype "passive"))
      (node (ref "R174") (pin "1") (pinfunction "1_1") (pintype "passive"))
    )
    (net (code "78") (name "Net-(Q75-C)") (class "Default")
      (node (ref "Q75") (pin "3") (pinfunction "C_3") (pintype "passive"))
      (node (ref "R156") (pin "1") (pinfunction "1_1") (pintype "passive"))
    )
    (net (code "79") (name "Net-(Q76-B)") (class "Default")
      (node (ref "Q76") (pin "1") (pinfunction "B_1") (pintype "passive"))
      (node (ref "R166") (pin "2") (pinfunction "2_2") (pintype "passive"))
      (node (ref "R175") (pin "1") (pinfunction "1_1") (pintype "passive"))
    )
    (net (code "80") (name "Net-(Q76-C)") (class "Default")
      (node (ref "Q76") (pin "3") (pinfunction "C_3") (pintype "passive"))
      (node (ref "R157") (pin "1") (pinfunction "1_1") (pintype "passive"))
    )
    (net (code "81") (name "Net-(Q77-B)") (class "Default")
      (node (ref "Q77") (pin "1") (pinfunction "B_1") (pintype "passive"))
      (node (ref "R167") (pin "2") (pinfunction "2_2") (pintype "passive"))
      (node (ref "R176") (pin "1") (pinfunction "1_1") (pintype "passive"))
    )
    (net (code "82") (name "Net-(Q77-C)") (class "Default")
      (node (ref "Q77") (pin "3") (pinfunction "C_3") (pintype "passive"))
      (node (ref "R158") (pin "1") (pinfunction "1_1") (pintype "passive"))
    )
    (net (code "83") (name "Net-(Q78-B)") (class "Default")
      (node (ref "Q78") (pin "1") (pinfunction "B_1") (pintype "passive"))
      (node (ref "R168") (pin "2") (pinfunction "2_2") (pintype "passive"))
      (node (ref "R177") (pin "1") (pinfunction "1_1") (pintype "passive"))
    )
    (net (code "84") (name "Net-(Q78-C)") (class "Default")
      (node (ref "Q78") (pin "3") (pinfunction "C_3") (pintype "passive"))
      (node (ref "R159") (pin "1") (pinfunction "1_1") (pintype "passive"))
    )
    (net (code "85") (name "Net-(Q79-B)") (class "Default")
      (node (ref "Q79") (pin "1") (pinfunction "B_1") (pintype "passive"))
      (node (ref "R169") (pin "2") (pinfunction "2_2") (pintype "passive"))
      (node (ref "R178") (pin "1") (pinfunction "1_1") (pintype "passive"))
    )
    (net (code "86") (name "Net-(Q79-C)") (class "Default")
      (node (ref "Q79") (pin "3") (pinfunction "C_3") (pintype "passive"))
      (node (ref "R160") (pin "1") (pinfunction "1_1") (pintype "passive"))
    )
    (net (code "87") (name "Net-(Q80-B)") (class "Default")
      (node (ref "Q80") (pin "1") (pinfunction "B_1") (pintype "passive"))
      (node (ref "R170") (pin "2") (pinfunction "2_2") (pintype "passive"))
      (node (ref "R179") (pin "1") (pinfunction "1_1") (pintype "passive"))
    )
    (net (code "88") (name "Net-(Q80-C)") (class "Default")
      (node (ref "Q80") (pin "3") (pinfunction "C_3") (pintype "passive"))
      (node (ref "R161") (pin "1") (pinfunction "1_1") (pintype "passive"))
    )
    (net (code "89") (name "Net-(Q81-B)") (class "Default")
      (node (ref "Q81") (pin "1") (pinfunction "B_1") (pintype "passive"))
      (node (ref "R171") (pin "2") (pinfunction "2_2") (pintype "passive"))
      (node (ref "R180") (pin "1") (pinfunction "1_1") (pintype "passive"))
    )
    (net (code "90") (name "Net-(Q81-C)") (class "Default")
      (node (ref "Q81") (pin "3") (pinfunction "C_3") (pintype "passive"))
      (node (ref "R162") (pin "1") (pinfunction "1_1") (pintype "passive"))
    )
    (net (code "91") (name "Net-(Q82-B)") (class "Default")
      (node (ref "Q82") (pin "1") (pinfunction "B_1") (pintype "passive"))
      (node (ref "R172") (pin "2") (pinfunction "2_2") (pintype "passive"))
      (node (ref "R181") (pin "1") (pinfunction "1_1") (pintype "passive"))
    )
    (net (code "92") (name "Net-(Q82-C)") (class "Default")
      (node (ref "Q82") (pin "3") (pinfunction "C_3") (pintype "passive"))
      (node (ref "R163") (pin "1") (pinfunction "1_1") (pintype "passive"))
    )
    (net (code "93") (name "Net-(Q83-B)") (class "Default")
      (node (ref "Q83") (pin "1") (pinfunction "B_1") (pintype "passive"))
      (node (ref "R173") (pin "2") (pinfunction "2_2") (pintype "passive"))
      (node (ref "R182") (pin "1") (pinfunction "1_1") (pintype "passive"))
    )
    (net (code "94") (name "Net-(Q83-C)") (class "Default")
      (node (ref "Q83") (pin "3") (pinfunction "C_3") (pintype "passive"))
      (node (ref "R164") (pin "1") (pinfunction "1_1") (pintype "passive"))
    )
    (net (code "95") (name "Net-(Q84-Pad1)") (class "Default")
      (node (ref "Q84") (pin "1") (pintype "power_in"))
      (node (ref "R190") (pin "2") (pinfunction "2_2") (pintype "passive"))
      (node (ref "R192") (pin "2") (pinfunction "2_2") (pintype "passive"))
    )
    (net (code "96") (name "Net-(Q85-Pad1)") (class "Default")
      (node (ref "Q85") (pin "1") (pintype "power_in"))
      (node (ref "R188") (pin "2") (pinfunction "2_2") (pintype "passive"))
      (node (ref "R193") (pin "2") (pinfunction "2_2") (pintype "passive"))
    )
    (net (code "97") (name "Net-(Q86-Pad1)") (class "Default")
      (node (ref "Q86") (pin "1") (pintype "power_in"))
      (node (ref "R191") (pin "2") (pinfunction "2_2") (pintype "passive"))
      (node (ref "R194") (pin "2") (pinfunction "2_2") (pintype "passive"))
    )
    (net (code "98") (name "Net-(Q87-Pad1)") (class "Default")
      (node (ref "Q87") (pin "1") (pintype "power_in"))
      (node (ref "R183") (pin "2") (pinfunction "2_2") (pintype "passive"))
      (node (ref "R195") (pin "2") (pinfunction "2_2") (pintype "passive"))
    )
    (net (code "99") (name "Net-(Q88-Pad1)") (class "Default")
      (node (ref "Q88") (pin "1") (pintype "power_in"))
      (node (ref "R189") (pin "2") (pinfunction "2_2") (pintype "passive"))
      (node (ref "R196") (pin "2") (pinfunction "2_2") (pintype "passive"))
    )
    (net (code "100") (name "Net-(Q89-Pad1)") (class "Default")
      (node (ref "Q89") (pin "1") (pintype "power_in"))
      (node (ref "R184") (pin "2") (pinfunction "2_2") (pintype "passive"))
      (node (ref "R197") (pin "2") (pinfunction "2_2") (pintype "passive"))
    )
    (net (code "101") (name "Net-(Q90-Pad1)") (class "Default")
      (node (ref "Q90") (pin "1") (pintype "power_in"))
      (node (ref "R186") (pin "2") (pinfunction "2_2") (pintype "passive"))
      (node (ref "R198") (pin "2") (pinfunction "2_2") (pintype "passive"))
    )
    (net (code "102") (name "Net-(Q91-Pad1)") (class "Default")
      (node (ref "Q91") (pin "1") (pintype "power_in"))
      (node (ref "R187") (pin "2") (pinfunction "2_2") (pintype "passive"))
      (node (ref "R199") (pin "2") (pinfunction "2_2") (pintype "passive"))
    )
    (net (code "103") (name "Net-(Q92-Pad1)") (class "Default")
      (node (ref "Q92") (pin "1") (pintype "power_in"))
      (node (ref "R185") (pin "2") (pinfunction "2_2") (pintype "passive"))
      (node (ref "R200") (pin "2") (pinfunction "2_2") (pintype "passive"))
    )
    (net (code "104") (name "Net-(Q93-B)") (class "Default")
      (node (ref "Q93") (pin "1") (pinfunction "B_1") (pintype "passive"))
      (node (ref "R201") (pin "2") (pinfunction "2_2") (pintype "passive"))
      (node (ref "R210") (pin "1") (pinfunction "1_1") (pintype "passive"))
    )
    (net (code "105") (name "Net-(Q93-C)") (class "Default")
      (node (ref "Q93") (pin "3") (pinfunction "C_3") (pintype "passive"))
      (node (ref "R192") (pin "1") (pinfunction "1_1") (pintype "passive"))
    )
    (net (code "106") (name "Net-(Q94-B)") (class "Default")
      (node (ref "Q94") (pin "1") (pinfunction "B_1") (pintype "passive"))
      (node (ref "R202") (pin "2") (pinfunction "2_2") (pintype "passive"))
      (node (ref "R211") (pin "1") (pinfunction "1_1") (pintype "passive"))
    )
    (net (code "107") (name "Net-(Q94-C)") (class "Default")
      (node (ref "Q94") (pin "3") (pinfunction "C_3") (pintype "passive"))
      (node (ref "R193") (pin "1") (pinfunction "1_1") (pintype "passive"))
    )
    (net (code "108") (name "Net-(Q95-B)") (class "Default")
      (node (ref "Q95") (pin "1") (pinfunction "B_1") (pintype "passive"))
      (node (ref "R203") (pin "2") (pinfunction "2_2") (pintype "passive"))
      (node (ref "R212") (pin "1") (pinfunction "1_1") (pintype "passive"))
    )
    (net (code "109") (name "Net-(Q95-C)") (class "Default")
      (node (ref "Q95") (pin "3") (pinfunction "C_3") (pintype "passive"))
      (node (ref "R194") (pin "1") (pinfunction "1_1") (pintype "passive"))
    )
    (net (code "110") (name "Net-(Q96-B)") (class "Default")
      (node (ref "Q96") (pin "1") (pinfunction "B_1") (pintype "passive"))
      (node (ref "R204") (pin "2") (pinfunction "2_2") (pintype "passive"))
      (node (ref "R213") (pin "1") (pinfunction "1_1") (pintype "passive"))
    )
    (net (code "111") (name "Net-(Q96-C)") (class "Default")
      (node (ref "Q96") (pin "3") (pinfunction "C_3") (pintype "passive"))
      (node (ref "R195") (pin "1") (pinfunction "1_1") (pintype "passive"))
    )
    (net (code "112") (name "Net-(Q97-B)") (class "Default")
      (node (ref "Q97") (pin "1") (pinfunction "B_1") (pintype "passive"))
      (node (ref "R205") (pin "2") (pinfunction "2_2") (pintype "passive"))
      (node (ref "R214") (pin "1") (pinfunction "1_1") (pintype "passive"))
    )
    (net (code "113") (name "Net-(Q97-C)") (class "Default")
      (node (ref "Q97") (pin "3") (pinfunction "C_3") (pintype "passive"))
      (node (ref "R196") (pin "1") (pinfunction "1_1") (pintype "passive"))
    )
    (net (code "114") (name "Net-(Q98-B)") (class "Default")
      (node (ref "Q98") (pin "1") (pinfunction "B_1") (pintype "passive"))
      (node (ref "R206") (pin "2") (pinfunction "2_2") (pintype "passive"))
      (node (ref "R215") (pin "1") (pinfunction "1_1") (pintype "passive"))
    )
    (net (code "115") (name "Net-(Q98-C)") (class "Default")
      (node (ref "Q98") (pin "3") (pinfunction "C_3") (pintype "passive"))
      (node (ref "R197") (pin "1") (pinfunction "1_1") (pintype "passive"))
    )
    (net (code "116") (name "Net-(Q99-B)") (class "Default")
      (node (ref "Q99") (pin "1") (pinfunction "B_1") (pintype "passive"))
      (node (ref "R207") (pin "2") (pinfunction "2_2") (pintype "passive"))
      (node (ref "R216") (pin "1") (pinfunction "1_1") (pintype "passive"))
    )
    (net (code "117") (name "Net-(Q99-C)") (class "Default")
      (node (ref "Q99") (pin "3") (pinfunction "C_3") (pintype "passive"))
      (node (ref "R198") (pin "1") (pinfunction "1_1") (pintype "passive"))
    )
    (net (code "118") (name "Net-(Q100-B)") (class "Default")
      (node (ref "Q100") (pin "1") (pinfunction "B_1") (pintype "passive"))
      (node (ref "R208") (pin "2") (pinfunction "2_2") (pintype "passive"))
      (node (ref "R217") (pin "1") (pinfunction "1_1") (pintype "passive"))
    )
    (net (code "119") (name "Net-(Q100-C)") (class "Default")
      (node (ref "Q100") (pin "3") (pinfunction "C_3") (pintype "passive"))
      (node (ref "R199") (pin "1") (pinfunction "1_1") (pintype "passive"))
    )
    (net (code "120") (name "Net-(Q101-B)") (class "Default")
      (node (ref "Q101") (pin "1") (pinfunction "B_1") (pintype "passive"))
      (node (ref "R209") (pin "2") (pinfunction "2_2") (pintype "passive"))
      (node (ref "R218") (pin "1") (pinfunction "1_1") (pintype "passive"))
    )
    (net (code "121") (name "Net-(Q101-C)") (class "Default")
      (node (ref "Q101") (pin "3") (pinfunction "C_3") (pintype "passive"))
      (node (ref "R200") (pin "1") (pinfunction "1_1") (pintype "passive"))
    )
    (net (code "122") (name "Net-(Q102-Pad1)") (class "Default")
      (node (ref "Q102") (pin "1") (pintype "power_in"))
      (node (ref "R219") (pin "2") (pinfunction "2_2") (pintype "passive"))
      (node (ref "R228") (pin "2") (pinfunction "2_2") (pintype "passive"))
    )
    (net (code "123") (name "Net-(Q103-Pad1)") (class "Default")
      (node (ref "Q103") (pin "1") (pintype "power_in"))
      (node (ref "R220") (pin "2") (pinfunction "2_2") (pintype "passive"))
      (node (ref "R229") (pin "2") (pinfunction "2_2") (pintype "passive"))
    )
    (net (code "124") (name "Net-(Q104-Pad1)") (class "Default")
      (node (ref "Q104") (pin "1") (pintype "power_in"))
      (node (ref "R225") (pin "2") (pinfunction "2_2") (pintype "passive"))
      (node (ref "R230") (pin "2") (pinfunction "2_2") (pintype "passive"))
    )
    (net (code "125") (name "Net-(Q105-Pad1)") (class "Default")
      (node (ref "Q105") (pin "1") (pintype "power_in"))
      (node (ref "R221") (pin "2") (pinfunction "2_2") (pintype "passive"))
      (node (ref "R231") (pin "2") (pinfunction "2_2") (pintype "passive"))
    )
    (net (code "126") (name "Net-(Q106-Pad1)") (class "Default")
      (node (ref "Q106") (pin "1") (pintype "power_in"))
      (node (ref "R222") (pin "2") (pinfunction "2_2") (pintype "passive"))
      (node (ref "R232") (pin "2") (pinfunction "2_2") (pintype "passive"))
    )
    (net (code "127") (name "Net-(Q107-Pad1)") (class "Default")
      (node (ref "Q107") (pin "1") (pintype "power_in"))
      (node (ref "R224") (pin "2") (pinfunction "2_2") (pintype "passive"))
      (node (ref "R233") (pin "2") (pinfunction "2_2") (pintype "passive"))
    )
    (net (code "128") (name "Net-(Q108-Pad1)") (class "Default")
      (node (ref "Q108") (pin "1") (pintype "power_in"))
      (node (ref "R226") (pin "2") (pinfunction "2_2") (pintype "passive"))
      (node (ref "R234") (pin "2") (pinfunction "2_2") (pintype "passive"))
    )
    (net (code "129") (name "Net-(Q109-Pad1)") (class "Default")
      (node (ref "Q109") (pin "1") (pintype "power_in"))
      (node (ref "R223") (pin "2") (pinfunction "2_2") (pintype "passive"))
      (node (ref "R235") (pin "2") (pinfunction "2_2") (pintype "passive"))
    )
    (net (code "130") (name "Net-(Q110-Pad1)") (class "Default")
      (node (ref "Q110") (pin "1") (pintype "power_in"))
      (node (ref "R227") (pin "2") (pinfunction "2_2") (pintype "passive"))
      (node (ref "R236") (pin "2") (pinfunction "2_2") (pintype "passive"))
    )
    (net (code "131") (name "Net-(Q111-B)") (class "Default")
      (node (ref "Q111") (pin "1") (pinfunction "B_1") (pintype "passive"))
      (node (ref "R237") (pin "2") (pinfunction "2_2") (pintype "passive"))
      (node (ref "R246") (pin "1") (pinfunction "1_1") (pintype "passive"))
    )
    (net (code "132") (name "Net-(Q111-C)") (class "Default")
      (node (ref "Q111") (pin "3") (pinfunction "C_3") (pintype "passive"))
      (node (ref "R228") (pin "1") (pinfunction "1_1") (pintype "passive"))
    )
    (net (code "133") (name "Net-(Q112-B)") (class "Default")
      (node (ref "Q112") (pin "1") (pinfunction "B_1") (pintype "passive"))
      (node (ref "R238") (pin "2") (pinfunction "2_2") (pintype "passive"))
      (node (ref "R247") (pin "1") (pinfunction "1_1") (pintype "passive"))
    )
    (net (code "134") (name "Net-(Q112-C)") (class "Default")
      (node (ref "Q112") (pin "3") (pinfunction "C_3") (pintype "passive"))
      (node (ref "R229") (pin "1") (pinfunction "1_1") (pintype "passive"))
    )
    (net (code "135") (name "Net-(Q113-B)") (class "Default")
      (node (ref "Q113") (pin "1") (pinfunction "B_1") (pintype "passive"))
      (node (ref "R239") (pin "2") (pinfunction "2_2") (pintype "passive"))
      (node (ref "R248") (pin "1") (pinfunction "1_1") (pintype "passive"))
    )
    (net (code "136") (name "Net-(Q113-C)") (class "Default")
      (node (ref "Q113") (pin "3") (pinfunction "C_3") (pintype "passive"))
      (node (ref "R230") (pin "1") (pinfunction "1_1") (pintype "passive"))
    )
    (net (code "137") (name "Net-(Q114-B)") (class "Default")
      (node (ref "Q114") (pin "1") (pinfunction "B_1") (pintype "passive"))
      (node (ref "R240") (pin "2") (pinfunction "2_2") (pintype "passive"))
      (node (ref "R249") (pin "1") (pinfunction "1_1") (pintype "passive"))
    )
    (net (code "138") (name "Net-(Q114-C)") (class "Default")
      (node (ref "Q114") (pin "3") (pinfunction "C_3") (pintype "passive"))
      (node (ref "R231") (pin "1") (pinfunction "1_1") (pintype "passive"))
    )
    (net (code "139") (name "Net-(Q115-B)") (class "Default")
      (node (ref "Q115") (pin "1") (pinfunction "B_1") (pintype "passive"))
      (node (ref "R241") (pin "2") (pinfunction "2_2") (pintype "passive"))
      (node (ref "R250") (pin "1") (pinfunction "1_1") (pintype "passive"))
    )
    (net (code "140") (name "Net-(Q115-C)") (class "Default")
      (node (ref "Q115") (pin "3") (pinfunction "C_3") (pintype "passive"))
      (node (ref "R232") (pin "1") (pinfunction "1_1") (pintype "passive"))
    )
    (net (code "141") (name "Net-(Q116-B)") (class "Default")
      (node (ref "Q116") (pin "1") (pinfunction "B_1") (pintype "passive"))
      (node (ref "R242") (pin "2") (pinfunction "2_2") (pintype "passive"))
      (node (ref "R251") (pin "1") (pinfunction "1_1") (pintype "passive"))
    )
    (net (code "142") (name "Net-(Q116-C)") (class "Default")
      (node (ref "Q116") (pin "3") (pinfunction "C_3") (pintype "passive"))
      (node (ref "R233") (pin "1") (pinfunction "1_1") (pintype "passive"))
    )
    (net (code "143") (name "Net-(Q117-B)") (class "Default")
      (node (ref "Q117") (pin "1") (pinfunction "B_1") (pintype "passive"))
      (node (ref "R243") (pin "2") (pinfunction "2_2") (pintype "passive"))
      (node (ref "R252") (pin "1") (pinfunction "1_1") (pintype "passive"))
    )
    (net (code "144") (name "Net-(Q117-C)") (class "Default")
      (node (ref "Q117") (pin "3") (pinfunction "C_3") (pintype "passive"))
      (node (ref "R234") (pin "1") (pinfunction "1_1") (pintype "passive"))
    )
    (net (code "145") (name "Net-(Q118-B)") (class "Default")
      (node (ref "Q118") (pin "1") (pinfunction "B_1") (pintype "passive"))
      (node (ref "R244") (pin "2") (pinfunction "2_2") (pintype "passive"))
      (node (ref "R253") (pin "1") (pinfunction "1_1") (pintype "passive"))
    )
    (net (code "146") (name "Net-(Q118-C)") (class "Default")
      (node (ref "Q118") (pin "3") (pinfunction "C_3") (pintype "passive"))
      (node (ref "R235") (pin "1") (pinfunction "1_1") (pintype "passive"))
    )
    (net (code "147") (name "Net-(Q119-B)") (class "Default")
      (node (ref "Q119") (pin "1") (pinfunction "B_1") (pintype "passive"))
      (node (ref "R245") (pin "2") (pinfunction "2_2") (pintype "passive"))
      (node (ref "R254") (pin "1") (pinfunction "1_1") (pintype "passive"))
    )
    (net (code "148") (name "Net-(Q119-C)") (class "Default")
      (node (ref "Q119") (pin "3") (pinfunction "C_3") (pintype "passive"))
      (node (ref "R236") (pin "1") (pinfunction "1_1") (pintype "passive"))
    )
    (net (code "149") (name "Net-(Q120-Pad1)") (class "Default")
      (node (ref "Q120") (pin "1") (pintype "power_in"))
      (node (ref "R257") (pin "2") (pinfunction "2_2") (pintype "passive"))
      (node (ref "R260") (pin "2") (pinfunction "2_2") (pintype "passive"))
    )
    (net (code "150") (name "Net-(Q121-Pad1)") (class "Default")
      (node (ref "Q121") (pin "1") (pintype "power_in"))
      (node (ref "R258") (pin "2") (pinfunction "2_2") (pintype "passive"))
      (node (ref "R261") (pin "2") (pinfunction "2_2") (pintype "passive"))
    )
    (net (code "151") (name "Net-(Q122-Pad1)") (class "Default")
      (node (ref "Q122") (pin "1") (pintype "power_in"))
      (node (ref "R255") (pin "2") (pinfunction "2_2") (pintype "passive"))
      (node (ref "R262") (pin "2") (pinfunction "2_2") (pintype "passive"))
    )
    (net (code "152") (name "Net-(Q123-Pad1)") (class "Default")
      (node (ref "Q123") (pin "1") (pintype "power_in"))
      (node (ref "R259") (pin "2") (pinfunction "2_2") (pintype "passive"))
      (node (ref "R263") (pin "2") (pinfunction "2_2") (pintype "passive"))
    )
    (net (code "153") (name "Net-(Q124-Pad1)") (class "Default")
      (node (ref "Q124") (pin "1") (pintype "power_in"))
      (node (ref "R256") (pin "2") (pinfunction "2_2") (pintype "passive"))
      (node (ref "R264") (pin "2") (pinfunction "2_2") (pintype "passive"))
    )
    (net (code "154") (name "Net-(Q125-B)") (class "Default")
      (node (ref "Q125") (pin "1") (pinfunction "B_1") (pintype "passive"))
      (node (ref "R265") (pin "2") (pinfunction "2_2") (pintype "passive"))
      (node (ref "R270") (pin "1") (pinfunction "1_1") (pintype "passive"))
    )
    (net (code "155") (name "Net-(Q125-C)") (class "Default")
      (node (ref "Q125") (pin "3") (pinfunction "C_3") (pintype "passive"))
      (node (ref "R260") (pin "1") (pinfunction "1_1") (pintype "passive"))
    )
    (net (code "156") (name "Net-(Q126-B)") (class "Default")
      (node (ref "Q126") (pin "1") (pinfunction "B_1") (pintype "passive"))
      (node (ref "R266") (pin "2") (pinfunction "2_2") (pintype "passive"))
      (node (ref "R271") (pin "1") (pinfunction "1_1") (pintype "passive"))
    )
    (net (code "157") (name "Net-(Q126-C)") (class "Default")
      (node (ref "Q126") (pin "3") (pinfunction "C_3") (pintype "passive"))
      (node (ref "R261") (pin "1") (pinfunction "1_1") (pintype "passive"))
    )
    (net (code "158") (name "Net-(Q127-B)") (class "Default")
      (node (ref "Q127") (pin "1") (pinfunction "B_1") (pintype "passive"))
      (node (ref "R267") (pin "2") (pinfunction "2_2") (pintype "passive"))
      (node (ref "R272") (pin "1") (pinfunction "1_1") (pintype "passive"))
    )
    (net (code "159") (name "Net-(Q127-C)") (class "Default")
      (node (ref "Q127") (pin "3") (pinfunction "C_3") (pintype "passive"))
      (node (ref "R262") (pin "1") (pinfunction "1_1") (pintype "passive"))
    )
    (net (code "160") (name "Net-(Q128-B)") (class "Default")
      (node (ref "Q128") (pin "1") (pinfunction "B_1") (pintype "passive"))
      (node (ref "R268") (pin "2") (pinfunction "2_2") (pintype "passive"))
      (node (ref "R273") (pin "1") (pinfunction "1_1") (pintype "passive"))
    )
    (net (code "161") (name "Net-(Q128-C)") (class "Default")
      (node (ref "Q128") (pin "3") (pinfunction "C_3") (pintype "passive"))
      (node (ref "R263") (pin "1") (pinfunction "1_1") (pintype "passive"))
    )
    (net (code "162") (name "Net-(Q129-B)") (class "Default")
      (node (ref "Q129") (pin "1") (pinfunction "B_1") (pintype "passive"))
      (node (ref "R269") (pin "2") (pinfunction "2_2") (pintype "passive"))
      (node (ref "R274") (pin "1") (pinfunction "1_1") (pintype "passive"))
    )
    (net (code "163") (name "Net-(Q129-C)") (class "Default")
      (node (ref "Q129") (pin "3") (pinfunction "C_3") (pintype "passive"))
      (node (ref "R264") (pin "1") (pinfunction "1_1") (pintype "passive"))
    )
  )
)
